# tides2_v40.net
KiCad netlist of a schematic drawn in EAGLE
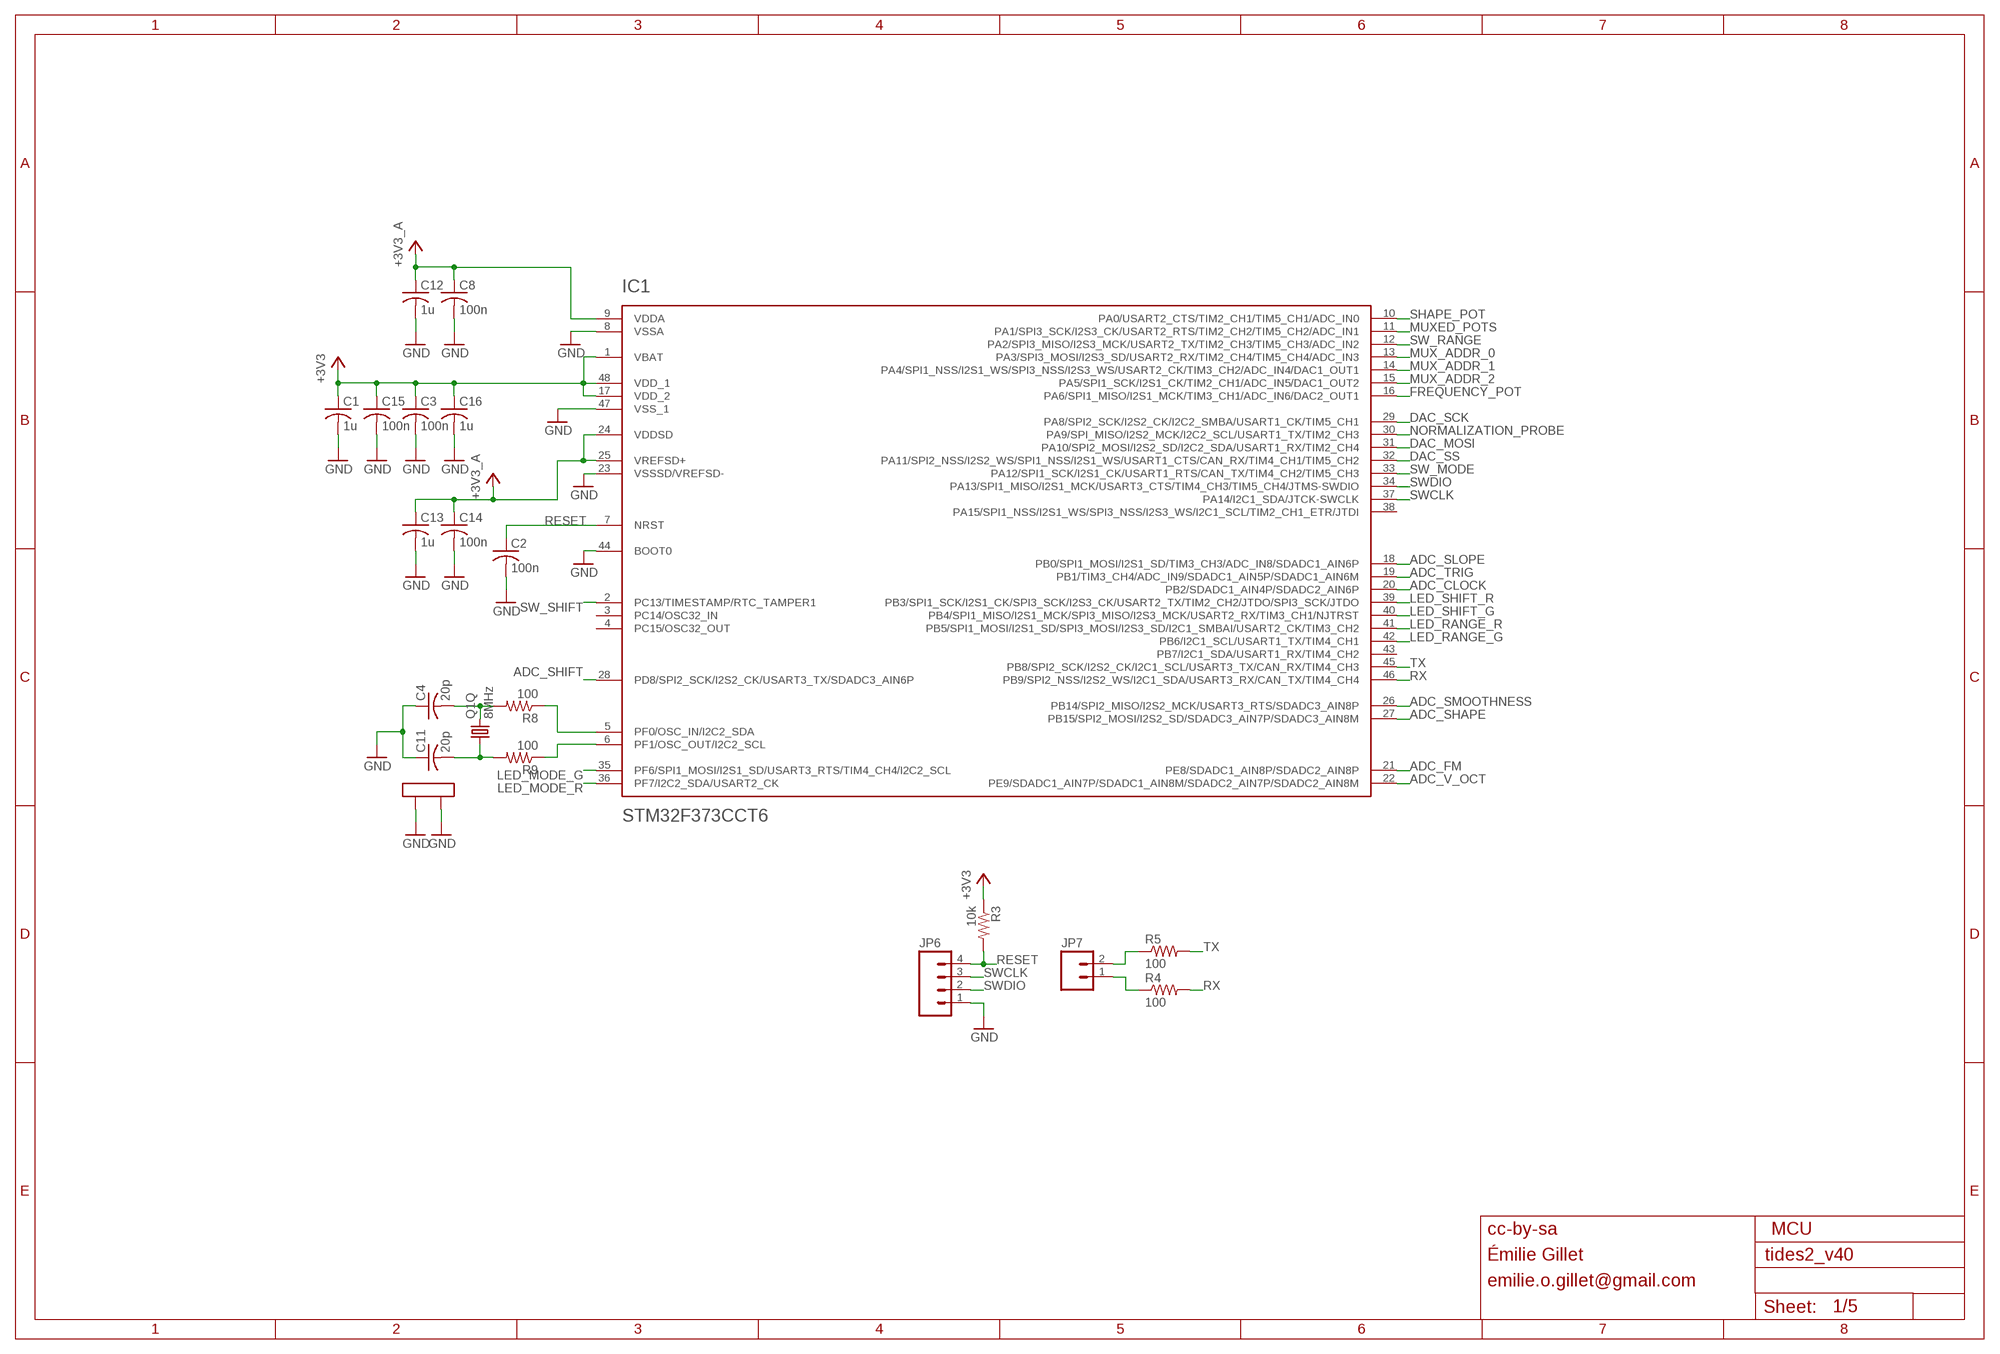
[diagram p0: schematic, sheet 1]
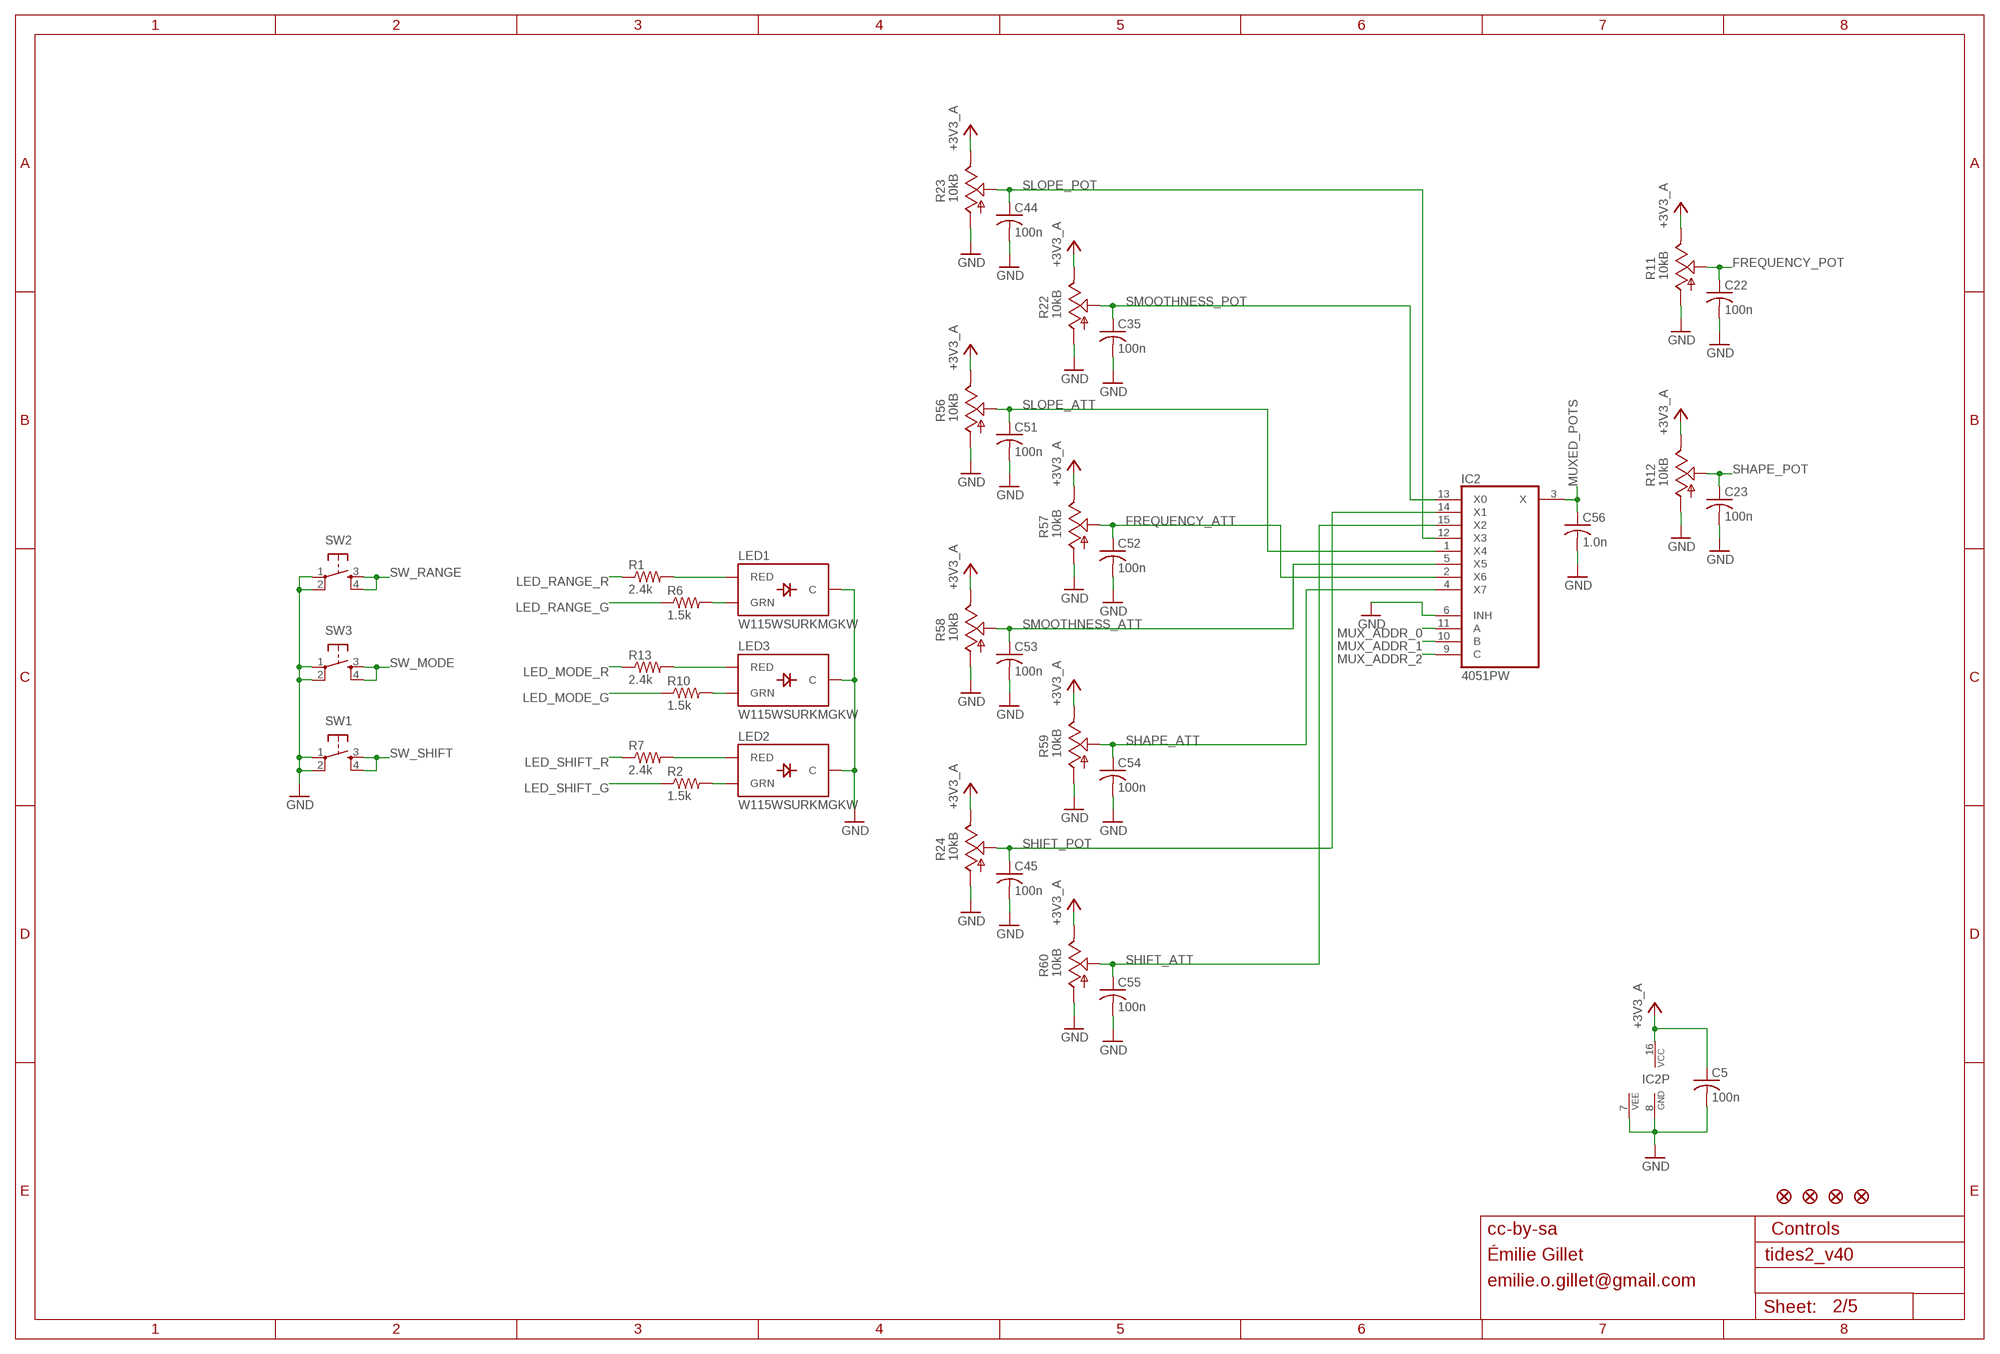
[diagram p1: schematic, sheet 2]
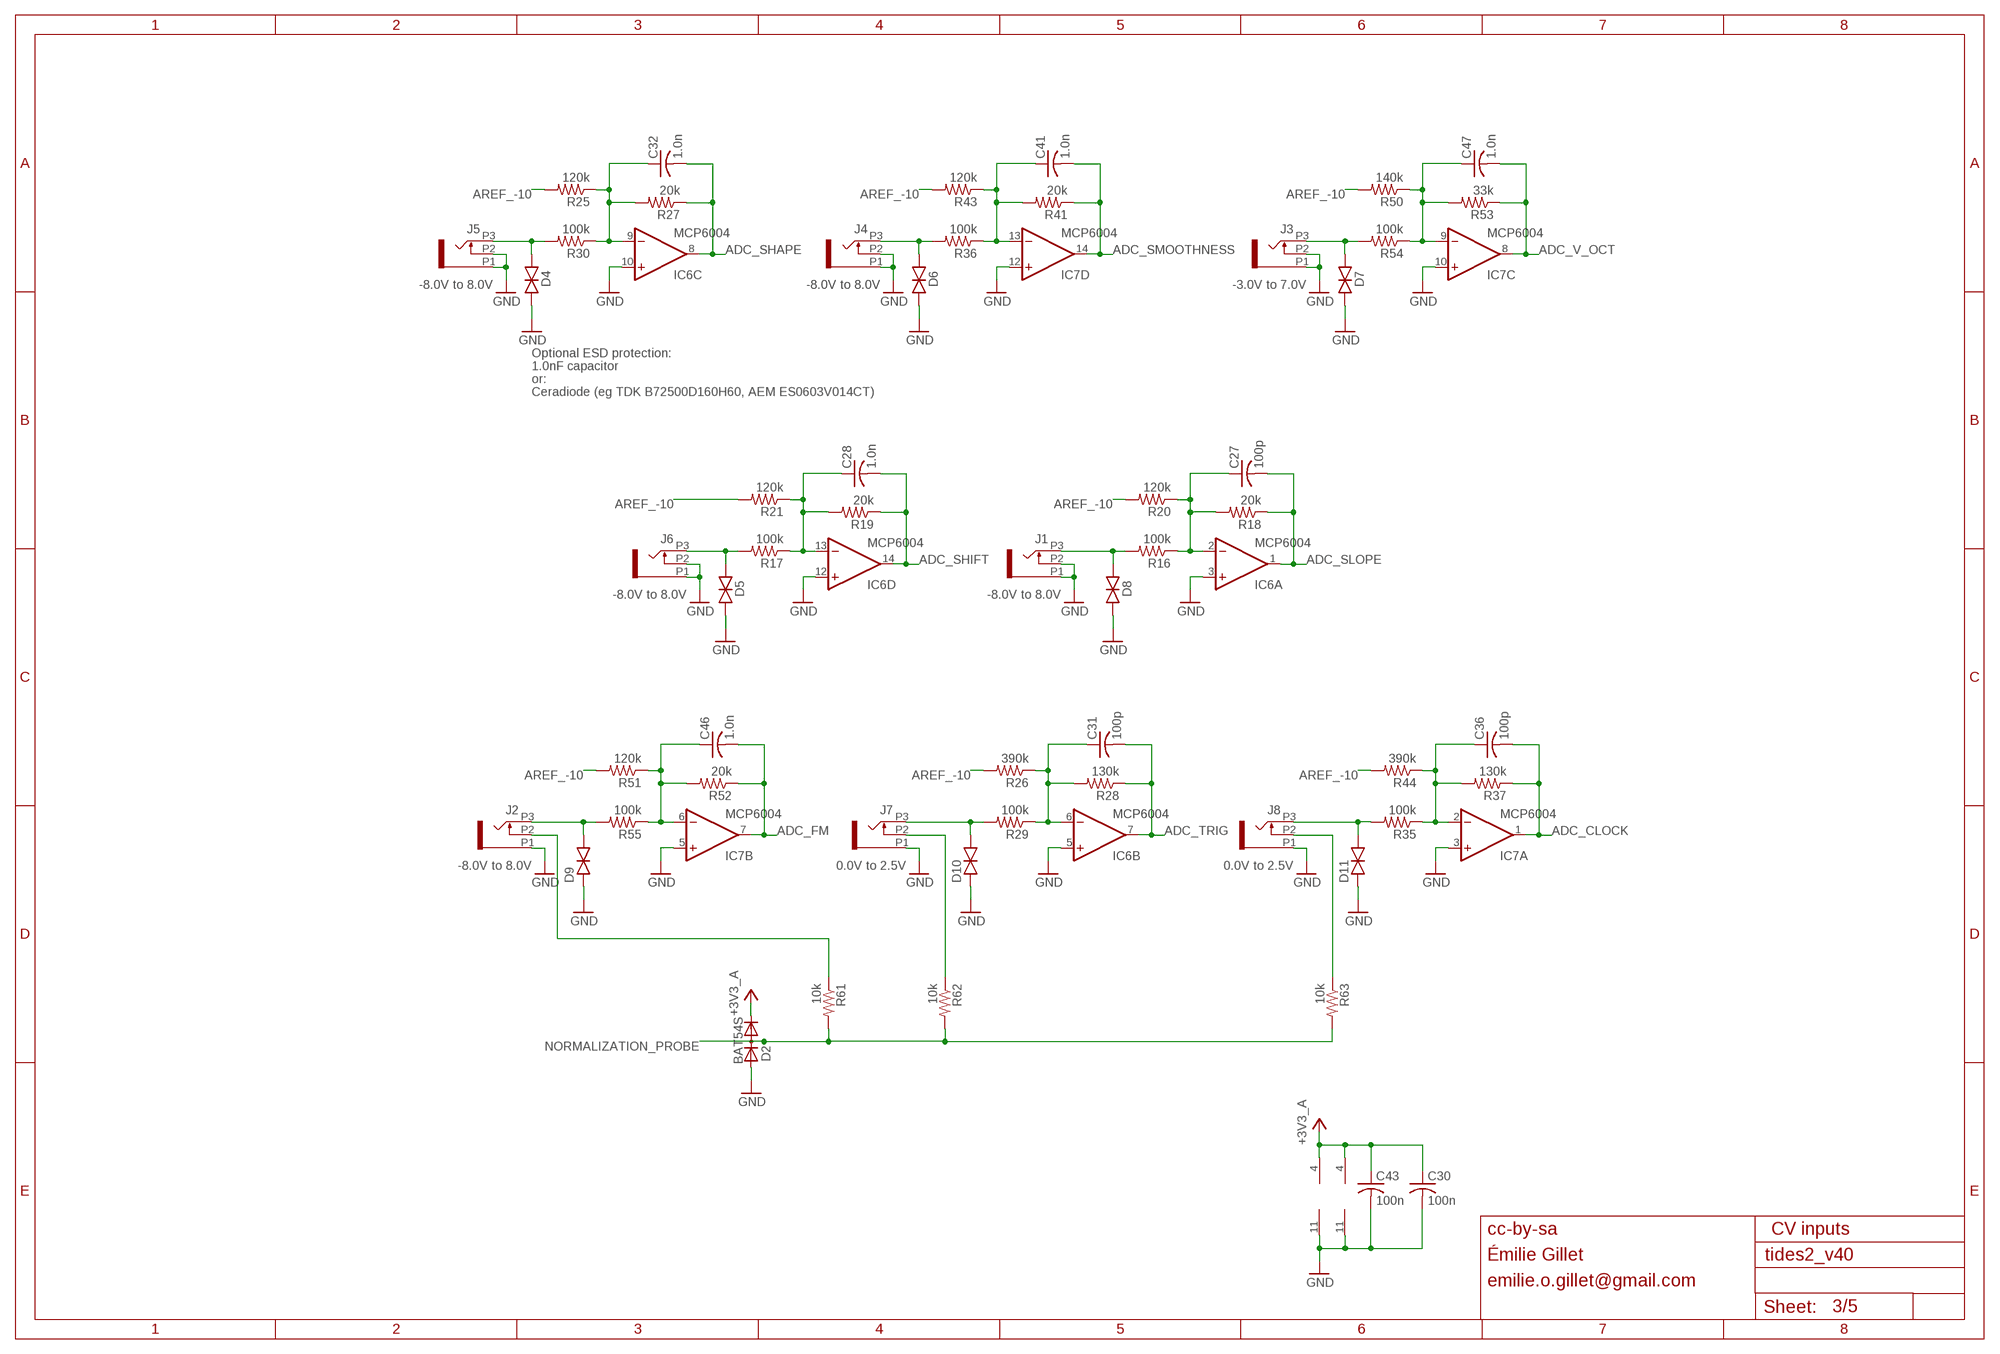
[diagram p2: schematic, sheet 3]
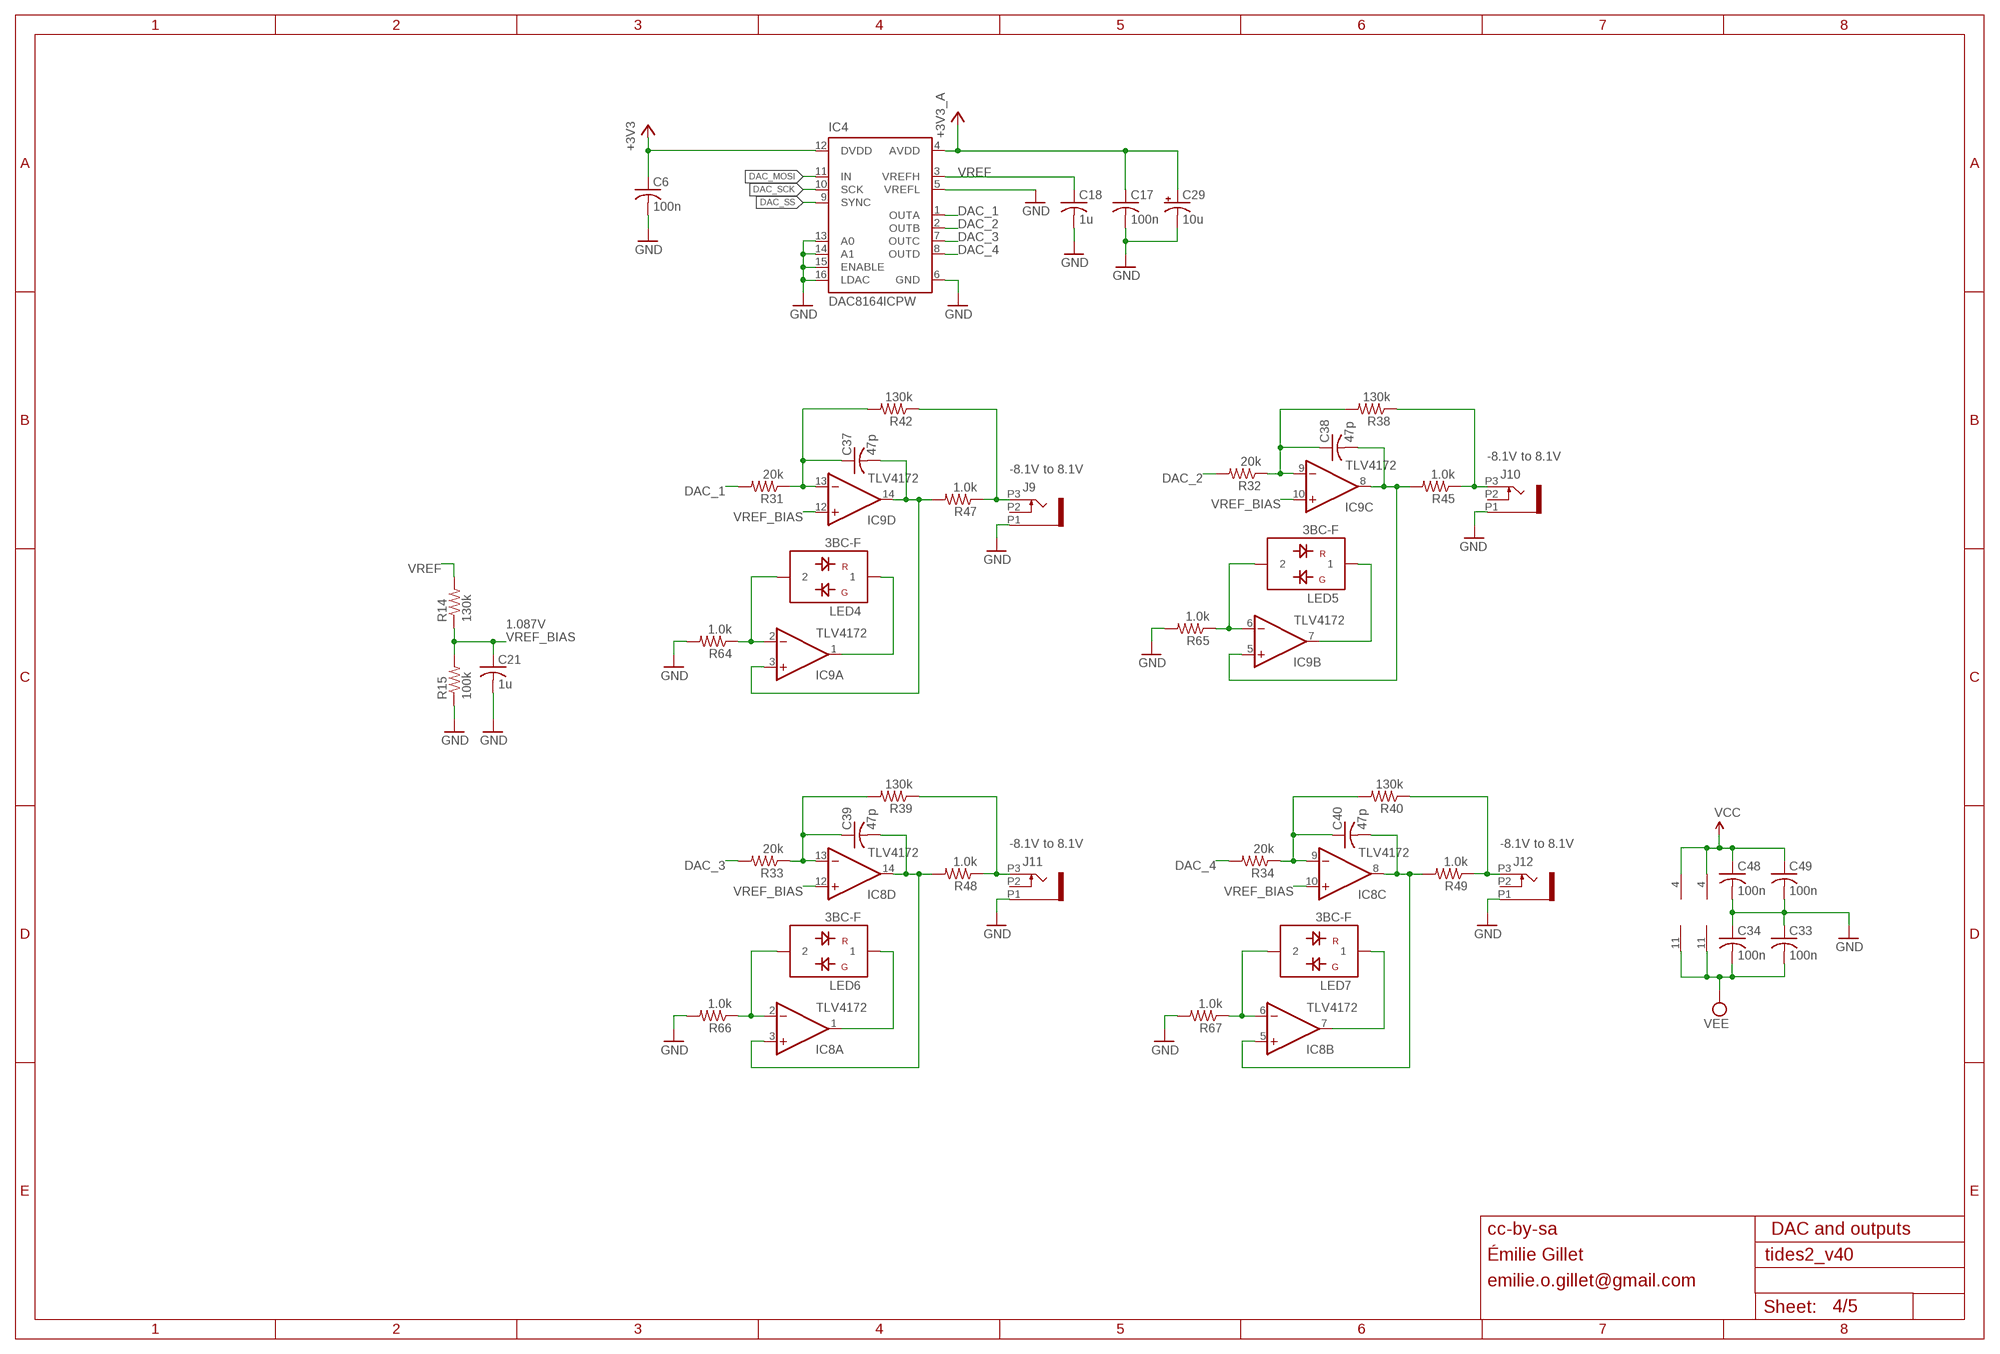
[diagram p3: schematic, sheet 4]
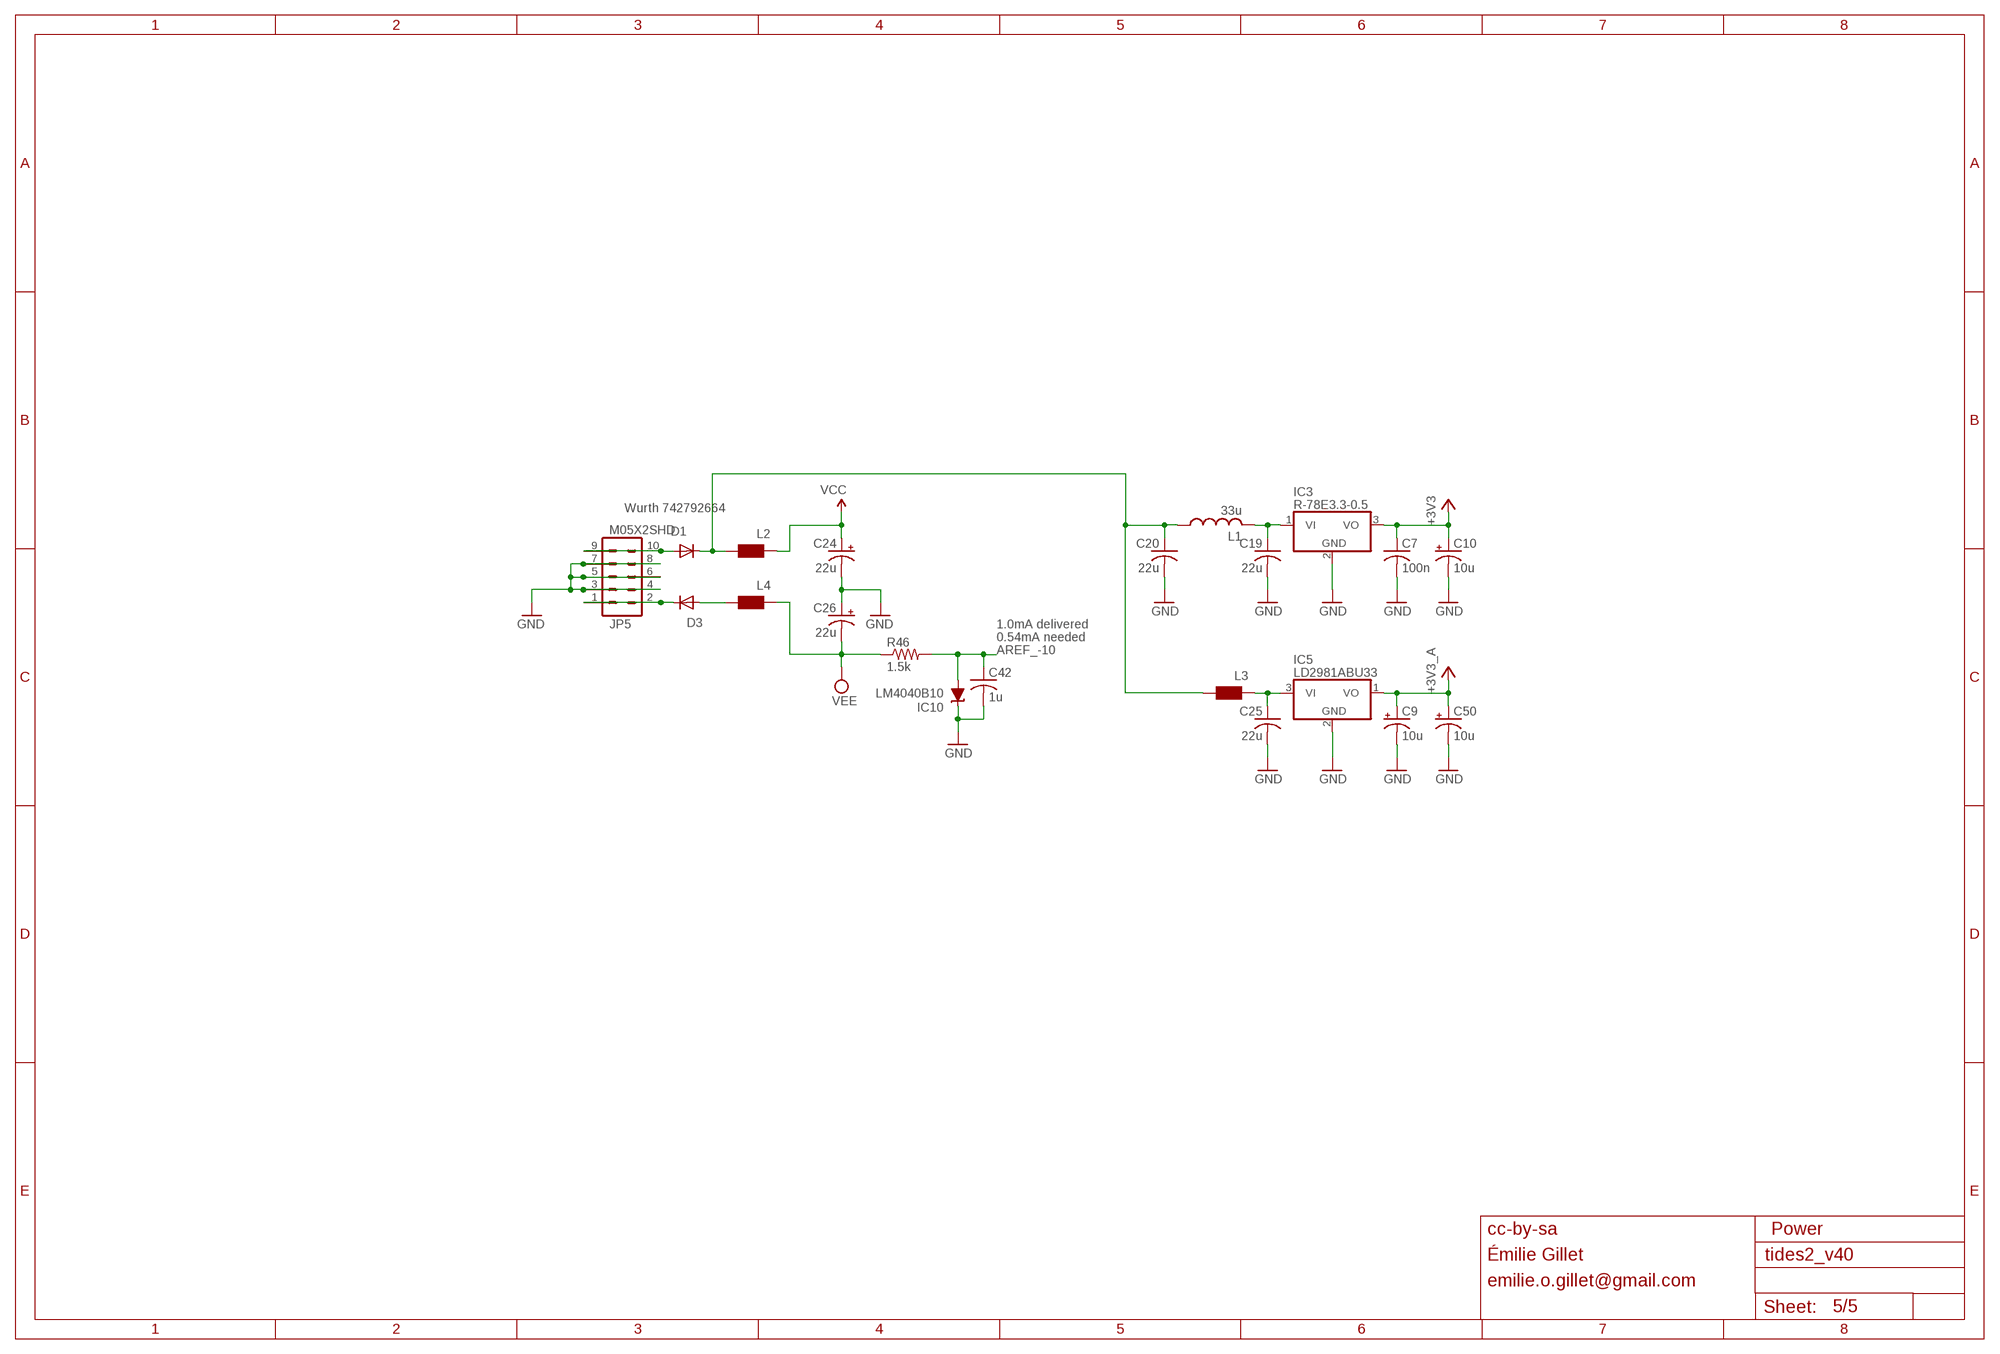
[diagram p4: schematic, sheet 5]

(export (version "E")
  (design (tool "Eeschema 10.0.6"))
  (components
    (comp (ref "C1")
      (value "1u")
      (footprint "eagle-import:C0402")
      (libsource (lib "eagle-import") (part "C-USC0402"))
    )
    (comp (ref "C2")
      (value "100n")
      (footprint "eagle-import:C0402")
      (libsource (lib "eagle-import") (part "C-USC0402"))
    )
    (comp (ref "C3")
      (value "100n")
      (footprint "eagle-import:C0402")
      (libsource (lib "eagle-import") (part "C-USC0402"))
    )
    (comp (ref "C4")
      (value "20p")
      (footprint "eagle-import:C0402")
      (libsource (lib "eagle-import") (part "C-USC0402"))
    )
    (comp (ref "C8")
      (value "100n")
      (footprint "eagle-import:C0402")
      (libsource (lib "eagle-import") (part "C-USC0402"))
    )
    (comp (ref "C11")
      (value "20p")
      (footprint "eagle-import:C0402")
      (libsource (lib "eagle-import") (part "C-USC0402"))
    )
    (comp (ref "C12")
      (value "1u")
      (footprint "eagle-import:C0402")
      (libsource (lib "eagle-import") (part "C-USC0402"))
    )
    (comp (ref "C13")
      (value "1u")
      (footprint "eagle-import:C0402")
      (libsource (lib "eagle-import") (part "C-USC0402"))
    )
    (comp (ref "C14")
      (value "100n")
      (footprint "eagle-import:C0402")
      (libsource (lib "eagle-import") (part "C-USC0402"))
    )
    (comp (ref "C15")
      (value "100n")
      (footprint "eagle-import:C0402")
      (libsource (lib "eagle-import") (part "C-USC0402"))
    )
    (comp (ref "C16")
      (value "1u")
      (footprint "eagle-import:C0402")
      (libsource (lib "eagle-import") (part "C-USC0402"))
    )
    (comp (ref "IC1")
      (value "STM32F373CCT6")
      (footprint "eagle-import:LQFP48")
      (libsource (lib "eagle-import") (part "STM32F373C"))
    )
    (comp (ref "JP6")
      (value "M04PTH")
      (footprint "eagle-import:1X04")
      (libsource (lib "eagle-import") (part "M04PTH"))
    )
    (comp (ref "JP7")
      (value "M02PTH")
      (footprint "eagle-import:1X02")
      (libsource (lib "eagle-import") (part "M02PTH"))
    )
    (comp (ref "Q1")
      (value "8MHz")
      (footprint "eagle-import:CTS406")
      (libsource (lib "eagle-import") (part "CRYSTAL"))
    )
    (comp (ref "R3")
      (value "10k")
      (footprint "eagle-import:R0402")
      (libsource (lib "eagle-import") (part "R-US_R0402"))
    )
    (comp (ref "R4")
      (value "100")
      (footprint "eagle-import:R0402")
      (libsource (lib "eagle-import") (part "R-US_R0402"))
    )
    (comp (ref "R5")
      (value "100")
      (footprint "eagle-import:R0402")
      (libsource (lib "eagle-import") (part "R-US_R0402"))
    )
    (comp (ref "R8")
      (value "100")
      (footprint "eagle-import:R0402")
      (libsource (lib "eagle-import") (part "R-US_R0402"))
    )
    (comp (ref "R9")
      (value "100")
      (footprint "eagle-import:R0402")
      (libsource (lib "eagle-import") (part "R-US_R0402"))
    )
    (comp (ref "C5")
      (value "100n")
      (footprint "eagle-import:C0402")
      (libsource (lib "eagle-import") (part "C-USC0402"))
    )
    (comp (ref "C22")
      (value "100n")
      (footprint "eagle-import:C0402")
      (libsource (lib "eagle-import") (part "C-USC0402"))
    )
    (comp (ref "C23")
      (value "100n")
      (footprint "eagle-import:C0402")
      (libsource (lib "eagle-import") (part "C-USC0402"))
    )
    (comp (ref "C35")
      (value "100n")
      (footprint "eagle-import:C0402")
      (libsource (lib "eagle-import") (part "C-USC0402"))
    )
    (comp (ref "C44")
      (value "100n")
      (footprint "eagle-import:C0402")
      (libsource (lib "eagle-import") (part "C-USC0402"))
    )
    (comp (ref "C45")
      (value "100n")
      (footprint "eagle-import:C0402")
      (libsource (lib "eagle-import") (part "C-USC0402"))
    )
    (comp (ref "C51")
      (value "100n")
      (footprint "eagle-import:C0402")
      (libsource (lib "eagle-import") (part "C-USC0402"))
    )
    (comp (ref "C52")
      (value "100n")
      (footprint "eagle-import:C0402")
      (libsource (lib "eagle-import") (part "C-USC0402"))
    )
    (comp (ref "C53")
      (value "100n")
      (footprint "eagle-import:C0402")
      (libsource (lib "eagle-import") (part "C-USC0402"))
    )
    (comp (ref "C54")
      (value "100n")
      (footprint "eagle-import:C0402")
      (libsource (lib "eagle-import") (part "C-USC0402"))
    )
    (comp (ref "C55")
      (value "100n")
      (footprint "eagle-import:C0402")
      (libsource (lib "eagle-import") (part "C-USC0402"))
    )
    (comp (ref "C56")
      (value "1.0n")
      (footprint "eagle-import:C0402")
      (libsource (lib "eagle-import") (part "C-USC0402"))
    )
    (comp (ref "IC2")
      (value "4051PW")
      (footprint "eagle-import:TSSOP16_065")
      (libsource (lib "eagle-import") (part "4051PW"))
    )
    (comp (ref "JP1")
      (value "FIDUCIAL1X2")
      (footprint "eagle-import:FIDUCIAL-1X2")
      (libsource (lib "eagle-import") (part "FIDUCIAL1X2"))
    )
    (comp (ref "JP2")
      (value "FIDUCIAL1X2")
      (footprint "eagle-import:FIDUCIAL-1X2")
      (libsource (lib "eagle-import") (part "FIDUCIAL1X2"))
    )
    (comp (ref "JP3")
      (value "FIDUCIAL1X2")
      (footprint "eagle-import:FIDUCIAL-1X2")
      (libsource (lib "eagle-import") (part "FIDUCIAL1X2"))
    )
    (comp (ref "JP4")
      (value "FIDUCIAL1X2")
      (footprint "eagle-import:FIDUCIAL-1X2")
      (libsource (lib "eagle-import") (part "FIDUCIAL1X2"))
    )
    (comp (ref "LED1")
      (value "W115WSURKMGKW")
      (footprint "eagle-import:LED-BICOLOR-THROUGHHOLE-2.54")
      (libsource (lib "eagle-import") (part "LED-BICOLOR-THROUGHHOLE2.54"))
    )
    (comp (ref "LED2")
      (value "W115WSURKMGKW")
      (footprint "eagle-import:LED-BICOLOR-THROUGHHOLE-2.54")
      (libsource (lib "eagle-import") (part "LED-BICOLOR-THROUGHHOLE2.54"))
    )
    (comp (ref "LED3")
      (value "W115WSURKMGKW")
      (footprint "eagle-import:LED-BICOLOR-THROUGHHOLE-2.54")
      (libsource (lib "eagle-import") (part "LED-BICOLOR-THROUGHHOLE2.54"))
    )
    (comp (ref "R1")
      (value "2.4k")
      (footprint "eagle-import:R0402")
      (libsource (lib "eagle-import") (part "R-US_R0402"))
    )
    (comp (ref "R2")
      (value "1.5k")
      (footprint "eagle-import:R0402")
      (libsource (lib "eagle-import") (part "R-US_R0402"))
    )
    (comp (ref "R6")
      (value "1.5k")
      (footprint "eagle-import:R0402")
      (libsource (lib "eagle-import") (part "R-US_R0402"))
    )
    (comp (ref "R7")
      (value "2.4k")
      (footprint "eagle-import:R0402")
      (libsource (lib "eagle-import") (part "R-US_R0402"))
    )
    (comp (ref "R10")
      (value "1.5k")
      (footprint "eagle-import:R0402")
      (libsource (lib "eagle-import") (part "R-US_R0402"))
    )
    (comp (ref "R11")
      (value "10kB")
      (footprint "eagle-import:ALPS_POT_VERTICAL_PS")
      (libsource (lib "eagle-import") (part "POT_USVERTICAL_PS"))
    )
    (comp (ref "R12")
      (value "10kB")
      (footprint "eagle-import:ALPS_POT_VERTICAL_PS")
      (libsource (lib "eagle-import") (part "POT_USVERTICAL_PS"))
    )
    (comp (ref "R13")
      (value "2.4k")
      (footprint "eagle-import:R0402")
      (libsource (lib "eagle-import") (part "R-US_R0402"))
    )
    (comp (ref "R22")
      (value "10kB")
      (footprint "eagle-import:ALPS_POT_VERTICAL_PS")
      (libsource (lib "eagle-import") (part "POT_USVERTICAL_PS"))
    )
    (comp (ref "R23")
      (value "10kB")
      (footprint "eagle-import:ALPS_POT_VERTICAL_PS")
      (libsource (lib "eagle-import") (part "POT_USVERTICAL_PS"))
    )
    (comp (ref "R24")
      (value "10kB")
      (footprint "eagle-import:ALPS_POT_VERTICAL_PS")
      (libsource (lib "eagle-import") (part "POT_USVERTICAL_PS"))
    )
    (comp (ref "R56")
      (value "10kB")
      (footprint "eagle-import:ALPS_POT_VERTICAL")
      (libsource (lib "eagle-import") (part "POT_USVERTICAL"))
    )
    (comp (ref "R57")
      (value "10kB")
      (footprint "eagle-import:ALPS_POT_VERTICAL")
      (libsource (lib "eagle-import") (part "POT_USVERTICAL"))
    )
    (comp (ref "R58")
      (value "10kB")
      (footprint "eagle-import:ALPS_POT_VERTICAL")
      (libsource (lib "eagle-import") (part "POT_USVERTICAL"))
    )
    (comp (ref "R59")
      (value "10kB")
      (footprint "eagle-import:ALPS_POT_VERTICAL")
      (libsource (lib "eagle-import") (part "POT_USVERTICAL"))
    )
    (comp (ref "R60")
      (value "10kB")
      (footprint "eagle-import:ALPS_POT_VERTICAL")
      (libsource (lib "eagle-import") (part "POT_USVERTICAL"))
    )
    (comp (ref "SW1")
      (value "TAC_SWITCHPTH")
      (footprint "eagle-import:TACTILE-PTH")
      (libsource (lib "eagle-import") (part "TAC_SWITCHPTH"))
    )
    (comp (ref "SW2")
      (value "TAC_SWITCHPTH")
      (footprint "eagle-import:TACTILE-PTH")
      (libsource (lib "eagle-import") (part "TAC_SWITCHPTH"))
    )
    (comp (ref "SW3")
      (value "TAC_SWITCHPTH")
      (footprint "eagle-import:TACTILE-PTH")
      (libsource (lib "eagle-import") (part "TAC_SWITCHPTH"))
    )
    (comp (ref "C7")
      (value "100n")
      (footprint "eagle-import:C0402")
      (libsource (lib "eagle-import") (part "C-USC0402"))
    )
    (comp (ref "C9")
      (value "10u")
      (footprint "eagle-import:PANASONIC_A")
      (libsource (lib "eagle-import") (part "CPOL-USA"))
    )
    (comp (ref "C10")
      (value "10u")
      (footprint "eagle-import:PANASONIC_A")
      (libsource (lib "eagle-import") (part "CPOL-USA"))
    )
    (comp (ref "C19")
      (value "22u")
      (footprint "eagle-import:C1206")
      (libsource (lib "eagle-import") (part "C-USC1206"))
    )
    (comp (ref "C20")
      (value "22u")
      (footprint "eagle-import:C1206")
      (libsource (lib "eagle-import") (part "C-USC1206"))
    )
    (comp (ref "C24")
      (value "22u")
      (footprint "eagle-import:PANASONIC_B")
      (libsource (lib "eagle-import") (part "CPOL-USB"))
    )
    (comp (ref "C25")
      (value "22u")
      (footprint "eagle-import:C1206")
      (libsource (lib "eagle-import") (part "C-USC1206"))
    )
    (comp (ref "C26")
      (value "22u")
      (footprint "eagle-import:PANASONIC_B")
      (libsource (lib "eagle-import") (part "CPOL-USB"))
    )
    (comp (ref "C42")
      (value "1u")
      (footprint "eagle-import:C0402")
      (libsource (lib "eagle-import") (part "C-USC0402"))
    )
    (comp (ref "C50")
      (value "10u")
      (footprint "eagle-import:PANASONIC_A")
      (libsource (lib "eagle-import") (part "CPOL-USA"))
    )
    (comp (ref "D1")
      (value "1N5819HW")
      (footprint "eagle-import:SOD123")
      (libsource (lib "eagle-import") (part "DIODE-SOD123"))
    )
    (comp (ref "D3")
      (value "1N5819HW")
      (footprint "eagle-import:SOD123")
      (libsource (lib "eagle-import") (part "DIODE-SOD123"))
    )
    (comp (ref "IC3")
      (value "R-78E3.3-0.5")
      (footprint "eagle-import:WE78")
      (libsource (lib "eagle-import") (part "WE173950378"))
    )
    (comp (ref "IC5")
      (value "LD2981ABU33")
      (footprint "eagle-import:SOT89")
      (libsource (lib "eagle-import") (part "LD2981ABU"))
    )
    (comp (ref "IC10")
      (value "LM4040B10")
      (footprint "eagle-import:DBZ_R-PDSO-G3")
      (libsource (lib "eagle-import") (part "LM4041DBZB12"))
    )
    (comp (ref "JP5")
      (value "M05X2SHD")
      (footprint "eagle-import:2X5-SHROUDED")
      (libsource (lib "eagle-import") (part "M05X2SHD"))
    )
    (comp (ref "L1")
      (value "33u")
      (footprint "eagle-import:L2012C")
      (libsource (lib "eagle-import") (part "L-USL2012C"))
    )
    (comp (ref "L2")
      (value "WE-CBF_0603")
      (footprint "eagle-import:0603")
      (libsource (lib "eagle-import") (part "WE-CBF_0603"))
    )
    (comp (ref "L3")
      (value "WE-CBF_0603")
      (footprint "eagle-import:0603")
      (libsource (lib "eagle-import") (part "WE-CBF_0603"))
    )
    (comp (ref "L4")
      (value "WE-CBF_0603")
      (footprint "eagle-import:0603")
      (libsource (lib "eagle-import") (part "WE-CBF_0603"))
    )
    (comp (ref "R46")
      (value "1.5k")
      (footprint "eagle-import:R0402")
      (libsource (lib "eagle-import") (part "R-US_R0402"))
    )
    (comp (ref "C27")
      (value "100p")
      (footprint "eagle-import:C0402")
      (libsource (lib "eagle-import") (part "C-USC0402"))
    )
    (comp (ref "C28")
      (value "1.0n")
      (footprint "eagle-import:C0402")
      (libsource (lib "eagle-import") (part "C-USC0402"))
    )
    (comp (ref "C30")
      (value "100n")
      (footprint "eagle-import:C0402")
      (libsource (lib "eagle-import") (part "C-USC0402"))
    )
    (comp (ref "C31")
      (value "100p")
      (footprint "eagle-import:C0402")
      (libsource (lib "eagle-import") (part "C-USC0402"))
    )
    (comp (ref "C32")
      (value "1.0n")
      (footprint "eagle-import:C0402")
      (libsource (lib "eagle-import") (part "C-USC0402"))
    )
    (comp (ref "C36")
      (value "100p")
      (footprint "eagle-import:C0402")
      (libsource (lib "eagle-import") (part "C-USC0402"))
    )
    (comp (ref "C41")
      (value "1.0n")
      (footprint "eagle-import:C0402")
      (libsource (lib "eagle-import") (part "C-USC0402"))
    )
    (comp (ref "C43")
      (value "100n")
      (footprint "eagle-import:C0402")
      (libsource (lib "eagle-import") (part "C-USC0402"))
    )
    (comp (ref "C46")
      (value "1.0n")
      (footprint "eagle-import:C0402")
      (libsource (lib "eagle-import") (part "C-USC0402"))
    )
    (comp (ref "C47")
      (value "1.0n")
      (footprint "eagle-import:C0402")
      (libsource (lib "eagle-import") (part "C-USC0402"))
    )
    (comp (ref "D2")
      (value "BAT54S")
      (footprint "eagle-import:SOT23")
      (libsource (lib "eagle-import") (part "DIODE_2CACA-SOT23"))
    )
    (comp (ref "D4")
      (value "TVS")
      (footprint "eagle-import:0603")
      (libsource (lib "eagle-import") (part "TVS"))
    )
    (comp (ref "D5")
      (value "TVS")
      (footprint "eagle-import:0603")
      (libsource (lib "eagle-import") (part "TVS"))
    )
    (comp (ref "D6")
      (value "TVS")
      (footprint "eagle-import:0603")
      (libsource (lib "eagle-import") (part "TVS"))
    )
    (comp (ref "D7")
      (value "TVS")
      (footprint "eagle-import:0603")
      (libsource (lib "eagle-import") (part "TVS"))
    )
    (comp (ref "D8")
      (value "TVS")
      (footprint "eagle-import:0603")
      (libsource (lib "eagle-import") (part "TVS"))
    )
    (comp (ref "D9")
      (value "TVS")
      (footprint "eagle-import:0603")
      (libsource (lib "eagle-import") (part "TVS"))
    )
    (comp (ref "D10")
      (value "TVS")
      (footprint "eagle-import:0603")
      (libsource (lib "eagle-import") (part "TVS"))
    )
    (comp (ref "D11")
      (value "TVS")
      (footprint "eagle-import:0603")
      (libsource (lib "eagle-import") (part "TVS"))
    )
    (comp (ref "IC6")
      (value "MCP6004")
      (footprint "eagle-import:TSSOP14_065")
      (libsource (lib "eagle-import") (part "TL074PW"))
    )
    (comp (ref "IC7")
      (value "MCP6004")
      (footprint "eagle-import:TSSOP14_065")
      (libsource (lib "eagle-import") (part "TL074PW"))
    )
    (comp (ref "J1")
      (value "PJ301_THONKICONN6")
      (footprint "eagle-import:WQP_PJ_301M6")
      (libsource (lib "eagle-import") (part "og-pj301_variations_PJ301_THONKICONN6"))
    )
    (comp (ref "J2")
      (value "PJ301_THONKICONN6")
      (footprint "eagle-import:WQP_PJ_301M6")
      (libsource (lib "eagle-import") (part "og-pj301_variations_PJ301_THONKICONN6"))
    )
    (comp (ref "J3")
      (value "PJ301_THONKICONN6")
      (footprint "eagle-import:WQP_PJ_301M6")
      (libsource (lib "eagle-import") (part "og-pj301_variations_PJ301_THONKICONN6"))
    )
    (comp (ref "J4")
      (value "PJ301_THONKICONN6")
      (footprint "eagle-import:WQP_PJ_301M6")
      (libsource (lib "eagle-import") (part "og-pj301_variations_PJ301_THONKICONN6"))
    )
    (comp (ref "J5")
      (value "PJ301_THONKICONN6")
      (footprint "eagle-import:WQP_PJ_301M6")
      (libsource (lib "eagle-import") (part "og-pj301_variations_PJ301_THONKICONN6"))
    )
    (comp (ref "J6")
      (value "PJ301_THONKICONN6")
      (footprint "eagle-import:WQP_PJ_301M6")
      (libsource (lib "eagle-import") (part "og-pj301_variations_PJ301_THONKICONN6"))
    )
    (comp (ref "J7")
      (value "PJ301_THONKICONN6")
      (footprint "eagle-import:WQP_PJ_301M6")
      (libsource (lib "eagle-import") (part "og-pj301_variations_PJ301_THONKICONN6"))
    )
    (comp (ref "J8")
      (value "PJ301_THONKICONN6")
      (footprint "eagle-import:WQP_PJ_301M6")
      (libsource (lib "eagle-import") (part "og-pj301_variations_PJ301_THONKICONN6"))
    )
    (comp (ref "R16")
      (value "100k")
      (footprint "eagle-import:R0402")
      (libsource (lib "eagle-import") (part "R-US_R0402"))
    )
    (comp (ref "R17")
      (value "100k")
      (footprint "eagle-import:R0402")
      (libsource (lib "eagle-import") (part "R-US_R0402"))
    )
    (comp (ref "R18")
      (value "20k")
      (footprint "eagle-import:R0402")
      (libsource (lib "eagle-import") (part "R-US_R0402"))
    )
    (comp (ref "R19")
      (value "20k")
      (footprint "eagle-import:R0402")
      (libsource (lib "eagle-import") (part "R-US_R0402"))
    )
    (comp (ref "R20")
      (value "120k")
      (footprint "eagle-import:R0402")
      (libsource (lib "eagle-import") (part "R-US_R0402"))
    )
    (comp (ref "R21")
      (value "120k")
      (footprint "eagle-import:R0402")
      (libsource (lib "eagle-import") (part "R-US_R0402"))
    )
    (comp (ref "R25")
      (value "120k")
      (footprint "eagle-import:R0402")
      (libsource (lib "eagle-import") (part "R-US_R0402"))
    )
    (comp (ref "R26")
      (value "390k")
      (footprint "eagle-import:R0402")
      (libsource (lib "eagle-import") (part "R-US_R0402"))
    )
    (comp (ref "R27")
      (value "20k")
      (footprint "eagle-import:R0402")
      (libsource (lib "eagle-import") (part "R-US_R0402"))
    )
    (comp (ref "R28")
      (value "130k")
      (footprint "eagle-import:R0402")
      (libsource (lib "eagle-import") (part "R-US_R0402"))
    )
    (comp (ref "R29")
      (value "100k")
      (footprint "eagle-import:R0402")
      (libsource (lib "eagle-import") (part "R-US_R0402"))
    )
    (comp (ref "R30")
      (value "100k")
      (footprint "eagle-import:R0402")
      (libsource (lib "eagle-import") (part "R-US_R0402"))
    )
    (comp (ref "R35")
      (value "100k")
      (footprint "eagle-import:R0402")
      (libsource (lib "eagle-import") (part "R-US_R0402"))
    )
    (comp (ref "R36")
      (value "100k")
      (footprint "eagle-import:R0402")
      (libsource (lib "eagle-import") (part "R-US_R0402"))
    )
    (comp (ref "R37")
      (value "130k")
      (footprint "eagle-import:R0402")
      (libsource (lib "eagle-import") (part "R-US_R0402"))
    )
    (comp (ref "R41")
      (value "20k")
      (footprint "eagle-import:R0402")
      (libsource (lib "eagle-import") (part "R-US_R0402"))
    )
    (comp (ref "R43")
      (value "120k")
      (footprint "eagle-import:R0402")
      (libsource (lib "eagle-import") (part "R-US_R0402"))
    )
    (comp (ref "R44")
      (value "390k")
      (footprint "eagle-import:R0402")
      (libsource (lib "eagle-import") (part "R-US_R0402"))
    )
    (comp (ref "R50")
      (value "140k")
      (footprint "eagle-import:R0402")
      (libsource (lib "eagle-import") (part "R-US_R0402"))
    )
    (comp (ref "R51")
      (value "120k")
      (footprint "eagle-import:R0402")
      (libsource (lib "eagle-import") (part "R-US_R0402"))
    )
    (comp (ref "R52")
      (value "20k")
      (footprint "eagle-import:R0402")
      (libsource (lib "eagle-import") (part "R-US_R0402"))
    )
    (comp (ref "R53")
      (value "33k")
      (footprint "eagle-import:R0402")
      (libsource (lib "eagle-import") (part "R-US_R0402"))
    )
    (comp (ref "R54")
      (value "100k")
      (footprint "eagle-import:R0402")
      (libsource (lib "eagle-import") (part "R-US_R0402"))
    )
    (comp (ref "R55")
      (value "100k")
      (footprint "eagle-import:R0402")
      (libsource (lib "eagle-import") (part "R-US_R0402"))
    )
    (comp (ref "R61")
      (value "10k")
      (footprint "eagle-import:R0402")
      (libsource (lib "eagle-import") (part "R-US_R0402"))
    )
    (comp (ref "R62")
      (value "10k")
      (footprint "eagle-import:R0402")
      (libsource (lib "eagle-import") (part "R-US_R0402"))
    )
    (comp (ref "R63")
      (value "10k")
      (footprint "eagle-import:R0402")
      (libsource (lib "eagle-import") (part "R-US_R0402"))
    )
    (comp (ref "C6")
      (value "100n")
      (footprint "eagle-import:C0402")
      (libsource (lib "eagle-import") (part "C-USC0402"))
    )
    (comp (ref "C17")
      (value "100n")
      (footprint "eagle-import:C0402")
      (libsource (lib "eagle-import") (part "C-USC0402"))
    )
    (comp (ref "C18")
      (value "1u")
      (footprint "eagle-import:C0402")
      (libsource (lib "eagle-import") (part "C-USC0402"))
    )
    (comp (ref "C21")
      (value "1u")
      (footprint "eagle-import:C0402")
      (libsource (lib "eagle-import") (part "C-USC0402"))
    )
    (comp (ref "C29")
      (value "10u")
      (footprint "eagle-import:PANASONIC_A")
      (libsource (lib "eagle-import") (part "CPOL-USA"))
    )
    (comp (ref "C33")
      (value "100n")
      (footprint "eagle-import:C0402")
      (libsource (lib "eagle-import") (part "C-USC0402"))
    )
    (comp (ref "C34")
      (value "100n")
      (footprint "eagle-import:C0402")
      (libsource (lib "eagle-import") (part "C-USC0402"))
    )
    (comp (ref "C37")
      (value "47p")
      (footprint "eagle-import:C0402")
      (libsource (lib "eagle-import") (part "C-USC0402"))
    )
    (comp (ref "C38")
      (value "47p")
      (footprint "eagle-import:C0402")
      (libsource (lib "eagle-import") (part "C-USC0402"))
    )
    (comp (ref "C39")
      (value "47p")
      (footprint "eagle-import:C0402")
      (libsource (lib "eagle-import") (part "C-USC0402"))
    )
    (comp (ref "C40")
      (value "47p")
      (footprint "eagle-import:C0402")
      (libsource (lib "eagle-import") (part "C-USC0402"))
    )
    (comp (ref "C48")
      (value "100n")
      (footprint "eagle-import:C0402")
      (libsource (lib "eagle-import") (part "C-USC0402"))
    )
    (comp (ref "C49")
      (value "100n")
      (footprint "eagle-import:C0402")
      (libsource (lib "eagle-import") (part "C-USC0402"))
    )
    (comp (ref "IC4")
      (value "DAC8164ICPW")
      (footprint "eagle-import:SOP65P640X110-16N")
      (libsource (lib "eagle-import") (part "DAC8564"))
    )
    (comp (ref "IC8")
      (value "TLV4172")
      (footprint "eagle-import:TSSOP14_065")
      (libsource (lib "eagle-import") (part "TL074PW"))
    )
    (comp (ref "IC9")
      (value "TLV4172")
      (footprint "eagle-import:TSSOP14_065")
      (libsource (lib "eagle-import") (part "TL074PW"))
    )
    (comp (ref "J9")
      (value "PJ301_THONKICONN6")
      (footprint "eagle-import:WQP_PJ_301M6")
      (libsource (lib "eagle-import") (part "PJ301_THONKICONN6"))
    )
    (comp (ref "J10")
      (value "PJ301_THONKICONN6")
      (footprint "eagle-import:WQP_PJ_301M6")
      (libsource (lib "eagle-import") (part "PJ301_THONKICONN6"))
    )
    (comp (ref "J11")
      (value "PJ301_THONKICONN6")
      (footprint "eagle-import:WQP_PJ_301M6")
      (libsource (lib "eagle-import") (part "PJ301_THONKICONN6"))
    )
    (comp (ref "J12")
      (value "PJ301_THONKICONN6")
      (footprint "eagle-import:WQP_PJ_301M6")
      (libsource (lib "eagle-import") (part "PJ301_THONKICONN6"))
    )
    (comp (ref "LED4")
      (value "3BC-F")
      (footprint "eagle-import:LED3MM")
      (libsource (lib "eagle-import") (part "LED-BICOLOR-SHARED-THROUGHHOLE"))
    )
    (comp (ref "LED5")
      (value "3BC-F")
      (footprint "eagle-import:LED3MM")
      (libsource (lib "eagle-import") (part "LED-BICOLOR-SHARED-THROUGHHOLE"))
    )
    (comp (ref "LED6")
      (value "3BC-F")
      (footprint "eagle-import:LED3MM")
      (libsource (lib "eagle-import") (part "LED-BICOLOR-SHARED-THROUGHHOLE"))
    )
    (comp (ref "LED7")
      (value "3BC-F")
      (footprint "eagle-import:LED3MM")
      (libsource (lib "eagle-import") (part "LED-BICOLOR-SHARED-THROUGHHOLE"))
    )
    (comp (ref "R14")
      (value "130k")
      (footprint "eagle-import:R0402")
      (libsource (lib "eagle-import") (part "R-US_R0402"))
    )
    (comp (ref "R15")
      (value "100k")
      (footprint "eagle-import:R0402")
      (libsource (lib "eagle-import") (part "R-US_R0402"))
    )
    (comp (ref "R31")
      (value "20k")
      (footprint "eagle-import:R0402")
      (libsource (lib "eagle-import") (part "R-US_R0402"))
    )
    (comp (ref "R32")
      (value "20k")
      (footprint "eagle-import:R0402")
      (libsource (lib "eagle-import") (part "R-US_R0402"))
    )
    (comp (ref "R33")
      (value "20k")
      (footprint "eagle-import:R0402")
      (libsource (lib "eagle-import") (part "R-US_R0402"))
    )
    (comp (ref "R34")
      (value "20k")
      (footprint "eagle-import:R0402")
      (libsource (lib "eagle-import") (part "R-US_R0402"))
    )
    (comp (ref "R38")
      (value "130k")
      (footprint "eagle-import:R0402")
      (libsource (lib "eagle-import") (part "R-US_R0402"))
    )
    (comp (ref "R39")
      (value "130k")
      (footprint "eagle-import:R0402")
      (libsource (lib "eagle-import") (part "R-US_R0402"))
    )
    (comp (ref "R40")
      (value "130k")
      (footprint "eagle-import:R0402")
      (libsource (lib "eagle-import") (part "R-US_R0402"))
    )
    (comp (ref "R42")
      (value "130k")
      (footprint "eagle-import:R0402")
      (libsource (lib "eagle-import") (part "R-US_R0402"))
    )
    (comp (ref "R45")
      (value "1.0k")
      (footprint "eagle-import:R0603")
      (libsource (lib "eagle-import") (part "R-US_R0603"))
    )
    (comp (ref "R47")
      (value "1.0k")
      (footprint "eagle-import:R0603")
      (libsource (lib "eagle-import") (part "R-US_R0603"))
    )
    (comp (ref "R48")
      (value "1.0k")
      (footprint "eagle-import:R0603")
      (libsource (lib "eagle-import") (part "R-US_R0603"))
    )
    (comp (ref "R49")
      (value "1.0k")
      (footprint "eagle-import:R0603")
      (libsource (lib "eagle-import") (part "R-US_R0603"))
    )
    (comp (ref "R64")
      (value "1.0k")
      (footprint "eagle-import:R0402")
      (libsource (lib "eagle-import") (part "R-US_R0402"))
    )
    (comp (ref "R65")
      (value "1.0k")
      (footprint "eagle-import:R0402")
      (libsource (lib "eagle-import") (part "R-US_R0402"))
    )
    (comp (ref "R66")
      (value "1.0k")
      (footprint "eagle-import:R0402")
      (libsource (lib "eagle-import") (part "R-US_R0402"))
    )
    (comp (ref "R67")
      (value "1.0k")
      (footprint "eagle-import:R0402")
      (libsource (lib "eagle-import") (part "R-US_R0402"))
    )
  )
  (nets
    (net (code "1") (name "+3V3") (class "Default")
      (node (ref "C1") (pin "1") (pinfunction "1_1") (pintype "passive"))
      (node (ref "C10") (pin "+") (pinfunction "+_+") (pintype "passive"))
      (node (ref "C15") (pin "1") (pinfunction "1_1") (pintype "passive"))
      (node (ref "C16") (pin "1") (pinfunction "1_1") (pintype "passive"))
      (node (ref "C3") (pin "1") (pinfunction "1_1") (pintype "passive"))
      (node (ref "C6") (pin "1") (pinfunction "1_1") (pintype "passive"))
      (node (ref "C7") (pin "1") (pinfunction "1_1") (pintype "passive"))
      (node (ref "IC1") (pin "1") (pinfunction "VBAT_1") (pintype "power_in"))
      (node (ref "IC1") (pin "17") (pinfunction "VDD_2_17") (pintype "power_in"))
      (node (ref "IC1") (pin "48") (pinfunction "VDD_1_48") (pintype "power_in"))
      (node (ref "IC3") (pin "3") (pinfunction "VO_3") (pintype "passive"))
      (node (ref "IC4") (pin "12") (pinfunction "DVDD_12") (pintype "power_in"))
      (node (ref "R3") (pin "1") (pinfunction "1_1") (pintype "passive"))
    )
    (net (code "2") (name "+3V3_A") (class "Default")
      (node (ref "C12") (pin "1") (pinfunction "1_1") (pintype "passive"))
      (node (ref "C13") (pin "1") (pinfunction "1_1") (pintype "passive"))
      (node (ref "C14") (pin "1") (pinfunction "1_1") (pintype "passive"))
      (node (ref "C17") (pin "1") (pinfunction "1_1") (pintype "passive"))
      (node (ref "C29") (pin "+") (pinfunction "+_+") (pintype "passive"))
      (node (ref "C30") (pin "1") (pinfunction "1_1") (pintype "passive"))
      (node (ref "C43") (pin "1") (pinfunction "1_1") (pintype "passive"))
      (node (ref "C5") (pin "1") (pinfunction "1_1") (pintype "passive"))
      (node (ref "C50") (pin "+") (pinfunction "+_+") (pintype "passive"))
      (node (ref "C8") (pin "1") (pinfunction "1_1") (pintype "passive"))
      (node (ref "C9") (pin "+") (pinfunction "+_+") (pintype "passive"))
      (node (ref "D2") (pin "2") (pinfunction "C_2") (pintype "passive"))
      (node (ref "IC1") (pin "24") (pinfunction "VDDSD_24") (pintype "power_in"))
      (node (ref "IC1") (pin "25") (pinfunction "VREFSD+_25") (pintype "power_in"))
      (node (ref "IC1") (pin "9") (pinfunction "VDDA_9") (pintype "power_in"))
      (node (ref "IC2") (pin "16") (pinfunction "VCC_16") (pintype "power_in"))
      (node (ref "IC4") (pin "4") (pinfunction "AVDD_4") (pintype "power_in"))
      (node (ref "IC5") (pin "1") (pinfunction "VO_1") (pintype "passive"))
      (node (ref "IC6") (pin "4") (pinfunction "V+_4") (pintype "power_in"))
      (node (ref "IC7") (pin "4") (pinfunction "V+_4") (pintype "power_in"))
      (node (ref "R11") (pin "P$1") (pinfunction "E_P$1") (pintype "passive"))
      (node (ref "R12") (pin "P$1") (pinfunction "E_P$1") (pintype "passive"))
      (node (ref "R22") (pin "P$1") (pinfunction "E_P$1") (pintype "passive"))
      (node (ref "R23") (pin "P$1") (pinfunction "E_P$1") (pintype "passive"))
      (node (ref "R24") (pin "P$1") (pinfunction "E_P$1") (pintype "passive"))
      (node (ref "R56") (pin "P$1") (pinfunction "E_P$1") (pintype "passive"))
      (node (ref "R57") (pin "P$1") (pinfunction "E_P$1") (pintype "passive"))
      (node (ref "R58") (pin "P$1") (pinfunction "E_P$1") (pintype "passive"))
      (node (ref "R59") (pin "P$1") (pinfunction "E_P$1") (pintype "passive"))
      (node (ref "R60") (pin "P$1") (pinfunction "E_P$1") (pintype "passive"))
    )
    (net (code "3") (name "ADC_CLOCK") (class "Default")
      (node (ref "C36") (pin "2") (pinfunction "2_2") (pintype "passive"))
      (node (ref "IC1") (pin "20") (pinfunction "PB2/SDADC1_AIN4P/SDADC2_AIN6P_20") (pintype "bidirectional"))
      (node (ref "IC7") (pin "1") (pinfunction "OUT_1") (pintype "output"))
      (node (ref "R37") (pin "1") (pinfunction "1_1") (pintype "passive"))
    )
    (net (code "4") (name "ADC_FM") (class "Default")
      (node (ref "C46") (pin "2") (pinfunction "2_2") (pintype "passive"))
      (node (ref "IC1") (pin "21") (pinfunction "PE8/SDADC1_AIN8P/SDADC2_AIN8P_21") (pintype "bidirectional"))
      (node (ref "IC7") (pin "7") (pinfunction "OUT_7") (pintype "output"))
      (node (ref "R52") (pin "1") (pinfunction "1_1") (pintype "passive"))
    )
    (net (code "5") (name "ADC_SHAPE") (class "Default")
      (node (ref "C32") (pin "2") (pinfunction "2_2") (pintype "passive"))
      (node (ref "IC1") (pin "27") (pinfunction "PB15/SPI2_MOSI/I2S2_SD/SDADC3_AIN7P/SDADC3_AIN8M_27") (pintype "bidirectional"))
      (node (ref "IC6") (pin "8") (pinfunction "OUT_8") (pintype "output"))
      (node (ref "R27") (pin "1") (pinfunction "1_1") (pintype "passive"))
    )
    (net (code "6") (name "ADC_SHIFT") (class "Default")
      (node (ref "C28") (pin "2") (pinfunction "2_2") (pintype "passive"))
      (node (ref "IC1") (pin "28") (pinfunction "PD8/SPI2_SCK/I2S2_CK/USART3_TX/SDADC3_AIN6P_28") (pintype "bidirectional"))
      (node (ref "IC6") (pin "14") (pinfunction "OUT_14") (pintype "output"))
      (node (ref "R19") (pin "1") (pinfunction "1_1") (pintype "passive"))
    )
    (net (code "7") (name "ADC_SLOPE") (class "Default")
      (node (ref "C27") (pin "2") (pinfunction "2_2") (pintype "passive"))
      (node (ref "IC1") (pin "18") (pinfunction "PB0/SPI1_MOSI/I2S1_SD/TIM3_CH3/ADC_IN8/SDADC1_AIN6P_18") (pintype "bidirectional"))
      (node (ref "IC6") (pin "1") (pinfunction "OUT_1") (pintype "output"))
      (node (ref "R18") (pin "1") (pinfunction "1_1") (pintype "passive"))
    )
    (net (code "8") (name "ADC_SMOOTHNESS") (class "Default")
      (node (ref "C41") (pin "2") (pinfunction "2_2") (pintype "passive"))
      (node (ref "IC1") (pin "26") (pinfunction "PB14/SPI2_MISO/I2S2_MCK/USART3_RTS/SDADC3_AIN8P_26") (pintype "bidirectional"))
      (node (ref "IC7") (pin "14") (pinfunction "OUT_14") (pintype "output"))
      (node (ref "R41") (pin "1") (pinfunction "1_1") (pintype "passive"))
    )
    (net (code "9") (name "ADC_TRIG") (class "Default")
      (node (ref "C31") (pin "2") (pinfunction "2_2") (pintype "passive"))
      (node (ref "IC1") (pin "19") (pinfunction "PB1/TIM3_CH4/ADC_IN9/SDADC1_AIN5P/SDADC1_AIN6M_19") (pintype "bidirectional"))
      (node (ref "IC6") (pin "7") (pinfunction "OUT_7") (pintype "output"))
      (node (ref "R28") (pin "1") (pinfunction "1_1") (pintype "passive"))
    )
    (net (code "10") (name "ADC_V_OCT") (class "Default")
      (node (ref "C47") (pin "2") (pinfunction "2_2") (pintype "passive"))
      (node (ref "IC1") (pin "22") (pinfunction "PE9/SDADC1_AIN7P/SDADC1_AIN8M/SDADC2_AIN7P/SDADC2_AIN8M_22") (pintype "bidirectional"))
      (node (ref "IC7") (pin "8") (pinfunction "OUT_8") (pintype "output"))
      (node (ref "R53") (pin "1") (pinfunction "1_1") (pintype "passive"))
    )
    (net (code "11") (name "AREF_-10") (class "Default")
      (node (ref "C42") (pin "1") (pinfunction "1_1") (pintype "passive"))
      (node (ref "IC10") (pin "2") (pinfunction "A_2") (pintype "passive"))
      (node (ref "R20") (pin "2") (pinfunction "2_2") (pintype "passive"))
      (node (ref "R21") (pin "2") (pinfunction "2_2") (pintype "passive"))
      (node (ref "R25") (pin "2") (pinfunction "2_2") (pintype "passive"))
      (node (ref "R26") (pin "2") (pinfunction "2_2") (pintype "passive"))
      (node (ref "R43") (pin "2") (pinfunction "2_2") (pintype "passive"))
      (node (ref "R44") (pin "2") (pinfunction "2_2") (pintype "passive"))
      (node (ref "R46") (pin "2") (pinfunction "2_2") (pintype "passive"))
      (node (ref "R50") (pin "2") (pinfunction "2_2") (pintype "passive"))
      (node (ref "R51") (pin "2") (pinfunction "2_2") (pintype "passive"))
    )
    (net (code "12") (name "DAC_1") (class "Default")
      (node (ref "IC4") (pin "1") (pinfunction "OUTA_1") (pintype "output"))
      (node (ref "R31") (pin "2") (pinfunction "2_2") (pintype "passive"))
    )
    (net (code "13") (name "DAC_2") (class "Default")
      (node (ref "IC4") (pin "2") (pinfunction "OUTB_2") (pintype "output"))
      (node (ref "R32") (pin "2") (pinfunction "2_2") (pintype "passive"))
    )
    (net (code "14") (name "DAC_3") (class "Default")
      (node (ref "IC4") (pin "7") (pinfunction "OUTC_7") (pintype "output"))
      (node (ref "R33") (pin "2") (pinfunction "2_2") (pintype "passive"))
    )
    (net (code "15") (name "DAC_4") (class "Default")
      (node (ref "IC4") (pin "8") (pinfunction "OUTD_8") (pintype "output"))
      (node (ref "R34") (pin "2") (pinfunction "2_2") (pintype "passive"))
    )
    (net (code "16") (name "DAC_MOSI") (class "Default")
      (node (ref "IC1") (pin "31") (pinfunction "PA10/SPI2_MOSI/I2S2_SD/I2C2_SDA/USART1_RX/TIM2_CH4_31") (pintype "bidirectional"))
      (node (ref "IC4") (pin "11") (pinfunction "IN_11") (pintype "input"))
    )
    (net (code "17") (name "DAC_SCK") (class "Default")
      (node (ref "IC1") (pin "29") (pinfunction "PA8/SPI2_SCK/I2S2_CK/I2C2_SMBA/USART1_CK/TIM5_CH1_29") (pintype "bidirectional"))
      (node (ref "IC4") (pin "10") (pinfunction "SCK_10") (pintype "input"))
    )
    (net (code "18") (name "DAC_SS") (class "Default")
      (node (ref "IC1") (pin "32") (pinfunction "PA11/SPI2_NSS/I2S2_WS/SPI1_NSS/I2S1_WS/USART1_CTS/CAN_RX/TIM4_CH1/TIM5_CH2_32") (pintype "bidirectional"))
      (node (ref "IC4") (pin "9") (pinfunction "SYNC_9") (pintype "input"))
    )
    (net (code "19") (name "FREQUENCY_ATT") (class "Default")
      (node (ref "C52") (pin "1") (pinfunction "1_1") (pintype "passive"))
      (node (ref "IC2") (pin "2") (pinfunction "X6_2") (pintype "bidirectional"))
      (node (ref "R57") (pin "P$2") (pinfunction "S_P$2") (pintype "passive"))
    )
    (net (code "20") (name "FREQUENCY_POT") (class "Default")
      (node (ref "C22") (pin "1") (pinfunction "1_1") (pintype "passive"))
      (node (ref "IC1") (pin "16") (pinfunction "PA6/SPI1_MISO/I2S1_MCK/TIM3_CH1/ADC_IN6/DAC2_OUT1_16") (pintype "bidirectional"))
      (node (ref "R11") (pin "P$2") (pinfunction "S_P$2") (pintype "passive"))
    )
    (net (code "21") (name "GND") (class "Default")
      (node (ref "C1") (pin "2") (pinfunction "2_2") (pintype "passive"))
      (node (ref "C10") (pin "-") (pinfunction "-_-") (pintype "passive"))
      (node (ref "C11") (pin "1") (pinfunction "1_1") (pintype "passive"))
      (node (ref "C12") (pin "2") (pinfunction "2_2") (pintype "passive"))
      (node (ref "C13") (pin "2") (pinfunction "2_2") (pintype "passive"))
      (node (ref "C14") (pin "2") (pinfunction "2_2") (pintype "passive"))
      (node (ref "C15") (pin "2") (pinfunction "2_2") (pintype "passive"))
      (node (ref "C16") (pin "2") (pinfunction "2_2") (pintype "passive"))
      (node (ref "C17") (pin "2") (pinfunction "2_2") (pintype "passive"))
      (node (ref "C18") (pin "2") (pinfunction "2_2") (pintype "passive"))
      (node (ref "C19") (pin "2") (pinfunction "2_2") (pintype "passive"))
      (node (ref "C2") (pin "2") (pinfunction "2_2") (pintype "passive"))
      (node (ref "C20") (pin "2") (pinfunction "2_2") (pintype "passive"))
      (node (ref "C21") (pin "2") (pinfunction "2_2") (pintype "passive"))
      (node (ref "C22") (pin "2") (pinfunction "2_2") (pintype "passive"))
      (node (ref "C23") (pin "2") (pinfunction "2_2") (pintype "passive"))
      (node (ref "C24") (pin "-") (pinfunction "-_-") (pintype "passive"))
      (node (ref "C25") (pin "2") (pinfunction "2_2") (pintype "passive"))
      (node (ref "C26") (pin "+") (pinfunction "+_+") (pintype "passive"))
      (node (ref "C29") (pin "-") (pinfunction "-_-") (pintype "passive"))
      (node (ref "C3") (pin "2") (pinfunction "2_2") (pintype "passive"))
      (node (ref "C30") (pin "2") (pinfunction "2_2") (pintype "passive"))
      (node (ref "C33") (pin "1") (pinfunction "1_1") (pintype "passive"))
      (node (ref "C34") (pin "1") (pinfunction "1_1") (pintype "passive"))
      (node (ref "C35") (pin "2") (pinfunction "2_2") (pintype "passive"))
      (node (ref "C4") (pin "1") (pinfunction "1_1") (pintype "passive"))
      (node (ref "C42") (pin "2") (pinfunction "2_2") (pintype "passive"))
      (node (ref "C43") (pin "2") (pinfunction "2_2") (pintype "passive"))
      (node (ref "C44") (pin "2") (pinfunction "2_2") (pintype "passive"))
      (node (ref "C45") (pin "2") (pinfunction "2_2") (pintype "passive"))
      (node (ref "C48") (pin "2") (pinfunction "2_2") (pintype "passive"))
      (node (ref "C49") (pin "2") (pinfunction "2_2") (pintype "passive"))
      (node (ref "C5") (pin "2") (pinfunction "2_2") (pintype "passive"))
      (node (ref "C50") (pin "-") (pinfunction "-_-") (pintype "passive"))
      (node (ref "C51") (pin "2") (pinfunction "2_2") (pintype "passive"))
      (node (ref "C52") (pin "2") (pinfunction "2_2") (pintype "passive"))
      (node (ref "C53") (pin "2") (pinfunction "2_2") (pintype "passive"))
      (node (ref "C54") (pin "2") (pinfunction "2_2") (pintype "passive"))
      (node (ref "C55") (pin "2") (pinfunction "2_2") (pintype "passive"))
      (node (ref "C56") (pin "2") (pinfunction "2_2") (pintype "passive"))
      (node (ref "C6") (pin "2") (pinfunction "2_2") (pintype "passive"))
      (node (ref "C7") (pin "2") (pinfunction "2_2") (pintype "passive"))
      (node (ref "C8") (pin "2") (pinfunction "2_2") (pintype "passive"))
      (node (ref "C9") (pin "-") (pinfunction "-_-") (pintype "passive"))
      (node (ref "D10") (pin "1") (pinfunction "A_1") (pintype "passive"))
      (node (ref "D11") (pin "1") (pinfunction "A_1") (pintype "passive"))
      (node (ref "D2") (pin "1") (pinfunction "A_1") (pintype "passive"))
      (node (ref "D4") (pin "1") (pinfunction "A_1") (pintype "passive"))
      (node (ref "D5") (pin "1") (pinfunction "A_1") (pintype "passive"))
      (node (ref "D6") (pin "1") (pinfunction "A_1") (pintype "passive"))
      (node (ref "D7") (pin "1") (pinfunction "A_1") (pintype "passive"))
      (node (ref "D8") (pin "1") (pinfunction "A_1") (pintype "passive"))
      (node (ref "D9") (pin "1") (pinfunction "A_1") (pintype "passive"))
      (node (ref "IC1") (pin "23") (pinfunction "VSSSD/VREFSD-_23") (pintype "power_in"))
      (node (ref "IC1") (pin "44") (pinfunction "BOOT0_44") (pintype "bidirectional"))
      (node (ref "IC1") (pin "47") (pinfunction "VSS_1_47") (pintype "power_in"))
      (node (ref "IC1") (pin "8") (pinfunction "VSSA_8") (pintype "power_in"))
      (node (ref "IC10") (pin "1") (pinfunction "C_1") (pintype "passive"))
      (node (ref "IC2") (pin "6") (pinfunction "INH_6") (pintype "input"))
      (node (ref "IC2") (pin "7") (pinfunction "VEE_7") (pintype "power_in"))
      (node (ref "IC2") (pin "8") (pinfunction "GND_8") (pintype "power_in"))
      (node (ref "IC3") (pin "2") (pinfunction "GND_2") (pintype "passive"))
      (node (ref "IC4") (pin "13") (pinfunction "A0_13") (pintype "input"))
      (node (ref "IC4") (pin "14") (pinfunction "A1_14") (pintype "input"))
      (node (ref "IC4") (pin "15") (pinfunction "ENABLE_15") (pintype "input"))
      (node (ref "IC4") (pin "16") (pinfunction "LDAC_16") (pintype "input"))
      (node (ref "IC4") (pin "5") (pinfunction "VREFL_5") (pintype "bidirectional"))
      (node (ref "IC4") (pin "6") (pinfunction "GND_6") (pintype "power_in"))
      (node (ref "IC5") (pin "2") (pinfunction "GND_2") (pintype "passive"))
      (node (ref "IC6") (pin "10") (pinfunction "+IN_10") (pintype "input"))
      (node (ref "IC6") (pin "11") (pinfunction "V-_11") (pintype "power_in"))
      (node (ref "IC6") (pin "12") (pinfunction "+IN_12") (pintype "input"))
      (node (ref "IC6") (pin "3") (pinfunction "+IN_3") (pintype "input"))
      (node (ref "IC6") (pin "5") (pinfunction "+IN_5") (pintype "input"))
      (node (ref "IC7") (pin "10") (pinfunction "+IN_10") (pintype "input"))
      (node (ref "IC7") (pin "11") (pinfunction "V-_11") (pintype "power_in"))
      (node (ref "IC7") (pin "12") (pinfunction "+IN_12") (pintype "input"))
      (node (ref "IC7") (pin "3") (pinfunction "+IN_3") (pintype "input"))
      (node (ref "IC7") (pin "5") (pinfunction "+IN_5") (pintype "input"))
      (node (ref "J1") (pin "P1") (pinfunction "1_P1") (pintype "passive"))
      (node (ref "J1") (pin "P2") (pinfunction "2_P2") (pintype "passive"))
      (node (ref "J10") (pin "P1") (pinfunction "1_P1") (pintype "passive"))
      (node (ref "J11") (pin "P1") (pinfunction "1_P1") (pintype "passive"))
      (node (ref "J12") (pin "P1") (pinfunction "1_P1") (pintype "passive"))
      (node (ref "J2") (pin "P1") (pinfunction "1_P1") (pintype "passive"))
      (node (ref "J3") (pin "P1") (pinfunction "1_P1") (pintype "passive"))
      (node (ref "J3") (pin "P2") (pinfunction "2_P2") (pintype "passive"))
      (node (ref "J4") (pin "P1") (pinfunction "1_P1") (pintype "passive"))
      (node (ref "J4") (pin "P2") (pinfunction "2_P2") (pintype "passive"))
      (node (ref "J5") (pin "P1") (pinfunction "1_P1") (pintype "passive"))
      (node (ref "J5") (pin "P2") (pinfunction "2_P2") (pintype "passive"))
      (node (ref "J6") (pin "P1") (pinfunction "1_P1") (pintype "passive"))
      (node (ref "J6") (pin "P2") (pinfunction "2_P2") (pintype "passive"))
      (node (ref "J7") (pin "P1") (pinfunction "1_P1") (pintype "passive"))
      (node (ref "J8") (pin "P1") (pinfunction "1_P1") (pintype "passive"))
      (node (ref "J9") (pin "P1") (pinfunction "1_P1") (pintype "passive"))
      (node (ref "JP5") (pin "3") (pinfunction "3_3") (pintype "passive"))
      (node (ref "JP5") (pin "4") (pinfunction "4_4") (pintype "passive"))
      (node (ref "JP5") (pin "5") (pinfunction "5_5") (pintype "passive"))
      (node (ref "JP5") (pin "6") (pinfunction "6_6") (pintype "passive"))
      (node (ref "JP5") (pin "7") (pinfunction "7_7") (pintype "passive"))
      (node (ref "JP5") (pin "8") (pinfunction "8_8") (pintype "passive"))
      (node (ref "JP6") (pin "1") (pinfunction "1_1") (pintype "passive"))
      (node (ref "LED1") (pin "2") (pinfunction "C_2") (pintype "bidirectional"))
      (node (ref "LED2") (pin "2") (pinfunction "C_2") (pintype "bidirectional"))
      (node (ref "LED3") (pin "2") (pinfunction "C_2") (pintype "bidirectional"))
      (node (ref "Q1") (pin "2") (pinfunction "LID1_2") (pintype "power_in"))
      (node (ref "Q1") (pin "4") (pinfunction "LID2_4") (pintype "power_in"))
      (node (ref "R11") (pin "P$3") (pinfunction "A_P$3") (pintype "passive"))
      (node (ref "R12") (pin "P$3") (pinfunction "A_P$3") (pintype "passive"))
      (node (ref "R15") (pin "1") (pinfunction "1_1") (pintype "passive"))
      (node (ref "R22") (pin "P$3") (pinfunction "A_P$3") (pintype "passive"))
      (node (ref "R23") (pin "P$3") (pinfunction "A_P$3") (pintype "passive"))
      (node (ref "R24") (pin "P$3") (pinfunction "A_P$3") (pintype "passive"))
      (node (ref "R56") (pin "P$3") (pinfunction "A_P$3") (pintype "passive"))
      (node (ref "R57") (pin "P$3") (pinfunction "A_P$3") (pintype "passive"))
      (node (ref "R58") (pin "P$3") (pinfunction "A_P$3") (pintype "passive"))
      (node (ref "R59") (pin "P$3") (pinfunction "A_P$3") (pintype "passive"))
      (node (ref "R60") (pin "P$3") (pinfunction "A_P$3") (pintype "passive"))
      (node (ref "R64") (pin "2") (pinfunction "2_2") (pintype "passive"))
      (node (ref "R65") (pin "2") (pinfunction "2_2") (pintype "passive"))
      (node (ref "R66") (pin "2") (pinfunction "2_2") (pintype "passive"))
      (node (ref "R67") (pin "2") (pinfunction "2_2") (pintype "passive"))
      (node (ref "SW1") (pin "1") (pinfunction "1_1") (pintype "passive"))
      (node (ref "SW1") (pin "2") (pinfunction "2_2") (pintype "passive"))
      (node (ref "SW2") (pin "1") (pinfunction "1_1") (pintype "passive"))
      (node (ref "SW2") (pin "2") (pinfunction "2_2") (pintype "passive"))
      (node (ref "SW3") (pin "1") (pinfunction "1_1") (pintype "passive"))
      (node (ref "SW3") (pin "2") (pinfunction "2_2") (pintype "passive"))
    )
    (net (code "22") (name "LED_MODE_G") (class "Default")
      (node (ref "IC1") (pin "35") (pinfunction "PF6/SPI1_MOSI/I2S1_SD/USART3_RTS/TIM4_CH4/I2C2_SCL_35") (pintype "bidirectional"))
      (node (ref "R10") (pin "1") (pinfunction "1_1") (pintype "passive"))
    )
    (net (code "23") (name "LED_MODE_R") (class "Default")
      (node (ref "IC1") (pin "36") (pinfunction "PF7/I2C2_SDA/USART2_CK_36") (pintype "bidirectional"))
      (node (ref "R13") (pin "1") (pinfunction "1_1") (pintype "passive"))
    )
    (net (code "24") (name "LED_RANGE_G") (class "Default")
      (node (ref "IC1") (pin "42") (pinfunction "PB6/I2C1_SCL/USART1_TX/TIM4_CH1_42") (pintype "bidirectional"))
      (node (ref "R6") (pin "1") (pinfunction "1_1") (pintype "passive"))
    )
    (net (code "25") (name "LED_RANGE_R") (class "Default")
      (node (ref "IC1") (pin "41") (pinfunction "PB5/SPI1_MOSI/I2S1_SD/SPI3_MOSI/I2S3_SD/I2C1_SMBAI/USART2_CK/TIM3_CH2_41") (pintype "bidirectional"))
      (node (ref "R1") (pin "1") (pinfunction "1_1") (pintype "passive"))
    )
    (net (code "26") (name "LED_SHIFT_G") (class "Default")
      (node (ref "IC1") (pin "40") (pinfunction "PB4/SPI1_MISO/I2S1_MCK/SPI3_MISO/I2S3_MCK/USART2_RX/TIM3_CH1/NJTRST_40") (pintype "bidirectional"))
      (node (ref "R2") (pin "1") (pinfunction "1_1") (pintype "passive"))
    )
    (net (code "27") (name "LED_SHIFT_R") (class "Default")
      (node (ref "IC1") (pin "39") (pinfunction "PB3/SPI1_SCK/I2S1_CK/SPI3_SCK/I2S3_CK/USART2_TX/TIM2_CH2/JTDO/SPI3_SCK/JTDO_39") (pintype "bidirectional"))
      (node (ref "R7") (pin "1") (pinfunction "1_1") (pintype "passive"))
    )
    (net (code "28") (name "MUXED_POTS") (class "Default")
      (node (ref "C56") (pin "1") (pinfunction "1_1") (pintype "passive"))
      (node (ref "IC1") (pin "11") (pinfunction "PA1/SPI3_SCK/I2S3_CK/USART2_RTS/TIM2_CH2/TIM5_CH2/ADC_IN1_11") (pintype "bidirectional"))
      (node (ref "IC2") (pin "3") (pinfunction "X_3") (pintype "bidirectional"))
    )
    (net (code "29") (name "MUX_ADDR_0") (class "Default")
      (node (ref "IC1") (pin "13") (pinfunction "PA3/SPI3_MOSI/I2S3_SD/USART2_RX/TIM2_CH4/TIM5_CH4/ADC_IN3_13") (pintype "bidirectional"))
      (node (ref "IC2") (pin "11") (pinfunction "A_11") (pintype "input"))
    )
    (net (code "30") (name "MUX_ADDR_1") (class "Default")
      (node (ref "IC1") (pin "14") (pinfunction "PA4/SPI1_NSS/I2S1_WS/SPI3_NSS/I2S3_WS/USART2_CK/TIM3_CH2/ADC_IN4/DAC1_OUT1_14") (pintype "bidirectional"))
      (node (ref "IC2") (pin "10") (pinfunction "B_10") (pintype "input"))
    )
    (net (code "31") (name "MUX_ADDR_2") (class "Default")
      (node (ref "IC1") (pin "15") (pinfunction "PA5/SPI1_SCK/I2S1_CK/TIM2_CH1/ADC_IN5/DAC1_OUT2_15") (pintype "bidirectional"))
      (node (ref "IC2") (pin "9") (pinfunction "C_9") (pintype "input"))
    )
    (net (code "32") (name "NORMALIZATION_PROBE") (class "Default")
      (node (ref "D2") (pin "3") (pinfunction "AC_3") (pintype "passive"))
      (node (ref "IC1") (pin "30") (pinfunction "PA9/SPI_MISO/I2S2_MCK/I2C2_SCL/USART1_TX/TIM2_CH3_30") (pintype "bidirectional"))
      (node (ref "R61") (pin "2") (pinfunction "2_2") (pintype "passive"))
      (node (ref "R62") (pin "2") (pinfunction "2_2") (pintype "passive"))
      (node (ref "R63") (pin "2") (pinfunction "2_2") (pintype "passive"))
    )
    (net (code "33") (name "Net-(C11-Pad2)") (class "Default")
      (node (ref "C11") (pin "2") (pinfunction "2_2") (pintype "passive"))
      (node (ref "Q1") (pin "1") (pinfunction "1_1") (pintype "passive"))
      (node (ref "R9") (pin "2") (pinfunction "2_2") (pintype "passive"))
    )
    (net (code "34") (name "Net-(C20-Pad1)") (class "Default")
      (node (ref "C20") (pin "1") (pinfunction "1_1") (pintype "passive"))
      (node (ref "D1") (pin "C") (pinfunction "C_C") (pintype "passive"))
      (node (ref "L1") (pin "1") (pinfunction "1_1") (pintype "passive"))
      (node (ref "L2") (pin "2") (pinfunction "2_2") (pintype "passive"))
      (node (ref "L3") (pin "2") (pinfunction "2_2") (pintype "passive"))
    )
    (net (code "35") (name "Net-(D1-PadA)") (class "Default")
      (node (ref "D1") (pin "A") (pinfunction "A_A") (pintype "passive"))
      (node (ref "JP5") (pin "10") (pinfunction "10_10") (pintype "passive"))
      (node (ref "JP5") (pin "9") (pinfunction "9_9") (pintype "passive"))
    )
    (net (code "36") (name "Net-(D3-PadA)") (class "Default")
      (node (ref "D3") (pin "A") (pinfunction "A_A") (pintype "passive"))
      (node (ref "L4") (pin "2") (pinfunction "2_2") (pintype "passive"))
    )
    (net (code "37") (name "Net-(D3-PadC)") (class "Default")
      (node (ref "D3") (pin "C") (pinfunction "C_C") (pintype "passive"))
      (node (ref "JP5") (pin "1") (pinfunction "1_1") (pintype "passive"))
      (node (ref "JP5") (pin "2") (pinfunction "2_2") (pintype "passive"))
    )
    (net (code "38") (name "Net-(D4-C)") (class "Default")
      (node (ref "D4") (pin "2") (pinfunction "C_2") (pintype "passive"))
      (node (ref "J5") (pin "P3") (pinfunction "3_P3") (pintype "passive"))
      (node (ref "R30") (pin "2") (pinfunction "2_2") (pintype "passive"))
    )
    (net (code "39") (name "Net-(D5-C)") (class "Default")
      (node (ref "D5") (pin "2") (pinfunction "C_2") (pintype "passive"))
      (node (ref "J6") (pin "P3") (pinfunction "3_P3") (pintype "passive"))
      (node (ref "R17") (pin "2") (pinfunction "2_2") (pintype "passive"))
    )
    (net (code "40") (name "Net-(D6-C)") (class "Default")
      (node (ref "D6") (pin "2") (pinfunction "C_2") (pintype "passive"))
      (node (ref "J4") (pin "P3") (pinfunction "3_P3") (pintype "passive"))
      (node (ref "R36") (pin "2") (pinfunction "2_2") (pintype "passive"))
    )
    (net (code "41") (name "Net-(D7-C)") (class "Default")
      (node (ref "D7") (pin "2") (pinfunction "C_2") (pintype "passive"))
      (node (ref "J3") (pin "P3") (pinfunction "3_P3") (pintype "passive"))
      (node (ref "R54") (pin "2") (pinfunction "2_2") (pintype "passive"))
    )
    (net (code "42") (name "Net-(D8-C)") (class "Default")
      (node (ref "D8") (pin "2") (pinfunction "C_2") (pintype "passive"))
      (node (ref "J1") (pin "P3") (pinfunction "3_P3") (pintype "passive"))
      (node (ref "R16") (pin "2") (pinfunction "2_2") (pintype "passive"))
    )
    (net (code "43") (name "Net-(D9-C)") (class "Default")
      (node (ref "D9") (pin "2") (pinfunction "C_2") (pintype "passive"))
      (node (ref "J2") (pin "P3") (pinfunction "3_P3") (pintype "passive"))
      (node (ref "R55") (pin "2") (pinfunction "2_2") (pintype "passive"))
    )
    (net (code "44") (name "Net-(D10-C)") (class "Default")
      (node (ref "D10") (pin "2") (pinfunction "C_2") (pintype "passive"))
      (node (ref "J7") (pin "P3") (pinfunction "3_P3") (pintype "passive"))
      (node (ref "R29") (pin "2") (pinfunction "2_2") (pintype "passive"))
    )
    (net (code "45") (name "Net-(D11-C)") (class "Default")
      (node (ref "D11") (pin "2") (pinfunction "C_2") (pintype "passive"))
      (node (ref "J8") (pin "P3") (pinfunction "3_P3") (pintype "passive"))
      (node (ref "R35") (pin "2") (pinfunction "2_2") (pintype "passive"))
    )
    (net (code "46") (name "Net-(IC1-PF0{slash}OSC_IN{slash}I2C2_SDA)") (class "Default")
      (node (ref "IC1") (pin "5") (pinfunction "PF0/OSC_IN/I2C2_SDA_5") (pintype "bidirectional"))
      (node (ref "R8") (pin "1") (pinfunction "1_1") (pintype "passive"))
    )
    (net (code "47") (name "Net-(IC1-PF1{slash}OSC_OUT{slash}I2C2_SCL)") (class "Default")
      (node (ref "IC1") (pin "6") (pinfunction "PF1/OSC_OUT/I2C2_SCL_6") (pintype "bidirectional"))
      (node (ref "R9") (pin "1") (pinfunction "1_1") (pintype "passive"))
    )
    (net (code "48") (name "Net-(IC3-VI)") (class "Default")
      (node (ref "C19") (pin "1") (pinfunction "1_1") (pintype "passive"))
      (node (ref "IC3") (pin "1") (pinfunction "VI_1") (pintype "input"))
      (node (ref "L1") (pin "2") (pinfunction "2_2") (pintype "passive"))
    )
    (net (code "49") (name "Net-(IC5-VI)") (class "Default")
      (node (ref "C25") (pin "1") (pinfunction "1_1") (pintype "passive"))
      (node (ref "IC5") (pin "3") (pinfunction "VI_3") (pintype "input"))
      (node (ref "L3") (pin "1") (pinfunction "1_1") (pintype "passive"))
    )
    (net (code "50") (name "Net-(IC6A--IN)") (class "Default")
      (node (ref "C27") (pin "1") (pinfunction "1_1") (pintype "passive"))
      (node (ref "IC6") (pin "2") (pinfunction "-IN_2") (pintype "input"))
      (node (ref "R16") (pin "1") (pinfunction "1_1") (pintype "passive"))
      (node (ref "R18") (pin "2") (pinfunction "2_2") (pintype "passive"))
      (node (ref "R20") (pin "1") (pinfunction "1_1") (pintype "passive"))
    )
    (net (code "51") (name "Net-(IC6B--IN)") (class "Default")
      (node (ref "C31") (pin "1") (pinfunction "1_1") (pintype "passive"))
      (node (ref "IC6") (pin "6") (pinfunction "-IN_6") (pintype "input"))
      (node (ref "R26") (pin "1") (pinfunction "1_1") (pintype "passive"))
      (node (ref "R28") (pin "2") (pinfunction "2_2") (pintype "passive"))
      (node (ref "R29") (pin "1") (pinfunction "1_1") (pintype "passive"))
    )
    (net (code "52") (name "Net-(IC6C--IN)") (class "Default")
      (node (ref "C32") (pin "1") (pinfunction "1_1") (pintype "passive"))
      (node (ref "IC6") (pin "9") (pinfunction "-IN_9") (pintype "input"))
      (node (ref "R25") (pin "1") (pinfunction "1_1") (pintype "passive"))
      (node (ref "R27") (pin "2") (pinfunction "2_2") (pintype "passive"))
      (node (ref "R30") (pin "1") (pinfunction "1_1") (pintype "passive"))
    )
    (net (code "53") (name "Net-(IC6D--IN)") (class "Default")
      (node (ref "C28") (pin "1") (pinfunction "1_1") (pintype "passive"))
      (node (ref "IC6") (pin "13") (pinfunction "-IN_13") (pintype "input"))
      (node (ref "R17") (pin "1") (pinfunction "1_1") (pintype "passive"))
      (node (ref "R19") (pin "2") (pinfunction "2_2") (pintype "passive"))
      (node (ref "R21") (pin "1") (pinfunction "1_1") (pintype "passive"))
    )
    (net (code "54") (name "Net-(IC7A--IN)") (class "Default")
      (node (ref "C36") (pin "1") (pinfunction "1_1") (pintype "passive"))
      (node (ref "IC7") (pin "2") (pinfunction "-IN_2") (pintype "input"))
      (node (ref "R35") (pin "1") (pinfunction "1_1") (pintype "passive"))
      (node (ref "R37") (pin "2") (pinfunction "2_2") (pintype "passive"))
      (node (ref "R44") (pin "1") (pinfunction "1_1") (pintype "passive"))
    )
    (net (code "55") (name "Net-(IC7B--IN)") (class "Default")
      (node (ref "C46") (pin "1") (pinfunction "1_1") (pintype "passive"))
      (node (ref "IC7") (pin "6") (pinfunction "-IN_6") (pintype "input"))
      (node (ref "R51") (pin "1") (pinfunction "1_1") (pintype "passive"))
      (node (ref "R52") (pin "2") (pinfunction "2_2") (pintype "passive"))
      (node (ref "R55") (pin "1") (pinfunction "1_1") (pintype "passive"))
    )
    (net (code "56") (name "Net-(IC7C--IN)") (class "Default")
      (node (ref "C47") (pin "1") (pinfunction "1_1") (pintype "passive"))
      (node (ref "IC7") (pin "9") (pinfunction "-IN_9") (pintype "input"))
      (node (ref "R50") (pin "1") (pinfunction "1_1") (pintype "passive"))
      (node (ref "R53") (pin "2") (pinfunction "2_2") (pintype "passive"))
      (node (ref "R54") (pin "1") (pinfunction "1_1") (pintype "passive"))
    )
    (net (code "57") (name "Net-(IC7D--IN)") (class "Default")
      (node (ref "C41") (pin "1") (pinfunction "1_1") (pintype "passive"))
      (node (ref "IC7") (pin "13") (pinfunction "-IN_13") (pintype "input"))
      (node (ref "R36") (pin "1") (pinfunction "1_1") (pintype "passive"))
      (node (ref "R41") (pin "2") (pinfunction "2_2") (pintype "passive"))
      (node (ref "R43") (pin "1") (pinfunction "1_1") (pintype "passive"))
    )
    (net (code "58") (name "Net-(IC8A-+IN)") (class "Default")
      (node (ref "C39") (pin "2") (pinfunction "2_2") (pintype "passive"))
      (node (ref "IC8") (pin "14") (pinfunction "OUT_14") (pintype "output"))
      (node (ref "IC8") (pin "3") (pinfunction "+IN_3") (pintype "input"))
      (node (ref "R48") (pin "2") (pinfunction "2_2") (pintype "passive"))
    )
    (net (code "59") (name "Net-(IC8A--IN)") (class "Default")
      (node (ref "IC8") (pin "2") (pinfunction "-IN_2") (pintype "input"))
      (node (ref "LED6") (pin "2") (pinfunction "2_2") (pintype "bidirectional"))
      (node (ref "R66") (pin "1") (pinfunction "1_1") (pintype "passive"))
    )
    (net (code "60") (name "Net-(IC8A-OUT)") (class "Default")
      (node (ref "IC8") (pin "1") (pinfunction "OUT_1") (pintype "output"))
      (node (ref "LED6") (pin "1") (pinfunction "1_1") (pintype "bidirectional"))
    )
    (net (code "61") (name "Net-(IC8B-+IN)") (class "Default")
      (node (ref "C40") (pin "2") (pinfunction "2_2") (pintype "passive"))
      (node (ref "IC8") (pin "5") (pinfunction "+IN_5") (pintype "input"))
      (node (ref "IC8") (pin "8") (pinfunction "OUT_8") (pintype "output"))
      (node (ref "R49") (pin "2") (pinfunction "2_2") (pintype "passive"))
    )
    (net (code "62") (name "Net-(IC8B--IN)") (class "Default")
      (node (ref "IC8") (pin "6") (pinfunction "-IN_6") (pintype "input"))
      (node (ref "LED7") (pin "2") (pinfunction "2_2") (pintype "bidirectional"))
      (node (ref "R67") (pin "1") (pinfunction "1_1") (pintype "passive"))
    )
    (net (code "63") (name "Net-(IC8B-OUT)") (class "Default")
      (node (ref "IC8") (pin "7") (pinfunction "OUT_7") (pintype "output"))
      (node (ref "LED7") (pin "1") (pinfunction "1_1") (pintype "bidirectional"))
    )
    (net (code "64") (name "Net-(IC8C--IN)") (class "Default")
      (node (ref "C40") (pin "1") (pinfunction "1_1") (pintype "passive"))
      (node (ref "IC8") (pin "9") (pinfunction "-IN_9") (pintype "input"))
      (node (ref "R34") (pin "1") (pinfunction "1_1") (pintype "passive"))
      (node (ref "R40") (pin "2") (pinfunction "2_2") (pintype "passive"))
    )
    (net (code "65") (name "Net-(IC8D--IN)") (class "Default")
      (node (ref "C39") (pin "1") (pinfunction "1_1") (pintype "passive"))
      (node (ref "IC8") (pin "13") (pinfunction "-IN_13") (pintype "input"))
      (node (ref "R33") (pin "1") (pinfunction "1_1") (pintype "passive"))
      (node (ref "R39") (pin "2") (pinfunction "2_2") (pintype "passive"))
    )
    (net (code "66") (name "Net-(IC9A-+IN)") (class "Default")
      (node (ref "C37") (pin "2") (pinfunction "2_2") (pintype "passive"))
      (node (ref "IC9") (pin "14") (pinfunction "OUT_14") (pintype "output"))
      (node (ref "IC9") (pin "3") (pinfunction "+IN_3") (pintype "input"))
      (node (ref "R47") (pin "2") (pinfunction "2_2") (pintype "passive"))
    )
    (net (code "67") (name "Net-(IC9A--IN)") (class "Default")
      (node (ref "IC9") (pin "2") (pinfunction "-IN_2") (pintype "input"))
      (node (ref "LED4") (pin "2") (pinfunction "2_2") (pintype "bidirectional"))
      (node (ref "R64") (pin "1") (pinfunction "1_1") (pintype "passive"))
    )
    (net (code "68") (name "Net-(IC9A-OUT)") (class "Default")
      (node (ref "IC9") (pin "1") (pinfunction "OUT_1") (pintype "output"))
      (node (ref "LED4") (pin "1") (pinfunction "1_1") (pintype "bidirectional"))
    )
    (net (code "69") (name "Net-(IC9B-+IN)") (class "Default")
      (node (ref "C38") (pin "2") (pinfunction "2_2") (pintype "passive"))
      (node (ref "IC9") (pin "5") (pinfunction "+IN_5") (pintype "input"))
      (node (ref "IC9") (pin "8") (pinfunction "OUT_8") (pintype "output"))
      (node (ref "R45") (pin "2") (pinfunction "2_2") (pintype "passive"))
    )
    (net (code "70") (name "Net-(IC9B--IN)") (class "Default")
      (node (ref "IC9") (pin "6") (pinfunction "-IN_6") (pintype "input"))
      (node (ref "LED5") (pin "2") (pinfunction "2_2") (pintype "bidirectional"))
      (node (ref "R65") (pin "1") (pinfunction "1_1") (pintype "passive"))
    )
    (net (code "71") (name "Net-(IC9B-OUT)") (class "Default")
      (node (ref "IC9") (pin "7") (pinfunction "OUT_7") (pintype "output"))
      (node (ref "LED5") (pin "1") (pinfunction "1_1") (pintype "bidirectional"))
    )
    (net (code "72") (name "Net-(IC9C--IN)") (class "Default")
      (node (ref "C38") (pin "1") (pinfunction "1_1") (pintype "passive"))
      (node (ref "IC9") (pin "9") (pinfunction "-IN_9") (pintype "input"))
      (node (ref "R32") (pin "1") (pinfunction "1_1") (pintype "passive"))
      (node (ref "R38") (pin "2") (pinfunction "2_2") (pintype "passive"))
    )
    (net (code "73") (name "Net-(IC9D--IN)") (class "Default")
      (node (ref "C37") (pin "1") (pinfunction "1_1") (pintype "passive"))
      (node (ref "IC9") (pin "13") (pinfunction "-IN_13") (pintype "input"))
      (node (ref "R31") (pin "1") (pinfunction "1_1") (pintype "passive"))
      (node (ref "R42") (pin "2") (pinfunction "2_2") (pintype "passive"))
    )
    (net (code "74") (name "Net-(J2-2)") (class "Default")
      (node (ref "J2") (pin "P2") (pinfunction "2_P2") (pintype "passive"))
      (node (ref "R61") (pin "1") (pinfunction "1_1") (pintype "passive"))
    )
    (net (code "75") (name "Net-(J7-2)") (class "Default")
      (node (ref "J7") (pin "P2") (pinfunction "2_P2") (pintype "passive"))
      (node (ref "R62") (pin "1") (pinfunction "1_1") (pintype "passive"))
    )
    (net (code "76") (name "Net-(J8-2)") (class "Default")
      (node (ref "J8") (pin "P2") (pinfunction "2_P2") (pintype "passive"))
      (node (ref "R63") (pin "1") (pinfunction "1_1") (pintype "passive"))
    )
    (net (code "77") (name "Net-(J9-3)") (class "Default")
      (node (ref "J9") (pin "P3") (pinfunction "3_P3") (pintype "passive"))
      (node (ref "R42") (pin "1") (pinfunction "1_1") (pintype "passive"))
      (node (ref "R47") (pin "1") (pinfunction "1_1") (pintype "passive"))
    )
    (net (code "78") (name "Net-(J10-3)") (class "Default")
      (node (ref "J10") (pin "P3") (pinfunction "3_P3") (pintype "passive"))
      (node (ref "R38") (pin "1") (pinfunction "1_1") (pintype "passive"))
      (node (ref "R45") (pin "1") (pinfunction "1_1") (pintype "passive"))
    )
    (net (code "79") (name "Net-(J11-3)") (class "Default")
      (node (ref "J11") (pin "P3") (pinfunction "3_P3") (pintype "passive"))
      (node (ref "R39") (pin "1") (pinfunction "1_1") (pintype "passive"))
      (node (ref "R48") (pin "1") (pinfunction "1_1") (pintype "passive"))
    )
    (net (code "80") (name "Net-(J12-3)") (class "Default")
      (node (ref "J12") (pin "P3") (pinfunction "3_P3") (pintype "passive"))
      (node (ref "R40") (pin "1") (pinfunction "1_1") (pintype "passive"))
      (node (ref "R49") (pin "1") (pinfunction "1_1") (pintype "passive"))
    )
    (net (code "81") (name "Net-(JP7-Pad1)") (class "Default")
      (node (ref "JP7") (pin "1") (pinfunction "1_1") (pintype "passive"))
      (node (ref "R4") (pin "1") (pinfunction "1_1") (pintype "passive"))
    )
    (net (code "82") (name "Net-(JP7-Pad2)") (class "Default")
      (node (ref "JP7") (pin "2") (pinfunction "2_2") (pintype "passive"))
      (node (ref "R5") (pin "1") (pinfunction "1_1") (pintype "passive"))
    )
    (net (code "83") (name "Net-(LED1-GRN)") (class "Default")
      (node (ref "LED1") (pin "1") (pinfunction "GRN_1") (pintype "bidirectional"))
      (node (ref "R6") (pin "2") (pinfunction "2_2") (pintype "passive"))
    )
    (net (code "84") (name "Net-(LED1-RED)") (class "Default")
      (node (ref "LED1") (pin "3") (pinfunction "RED_3") (pintype "bidirectional"))
      (node (ref "R1") (pin "2") (pinfunction "2_2") (pintype "passive"))
    )
    (net (code "85") (name "Net-(LED2-GRN)") (class "Default")
      (node (ref "LED2") (pin "1") (pinfunction "GRN_1") (pintype "bidirectional"))
      (node (ref "R2") (pin "2") (pinfunction "2_2") (pintype "passive"))
    )
    (net (code "86") (name "Net-(LED2-RED)") (class "Default")
      (node (ref "LED2") (pin "3") (pinfunction "RED_3") (pintype "bidirectional"))
      (node (ref "R7") (pin "2") (pinfunction "2_2") (pintype "passive"))
    )
    (net (code "87") (name "Net-(LED3-GRN)") (class "Default")
      (node (ref "LED3") (pin "1") (pinfunction "GRN_1") (pintype "bidirectional"))
      (node (ref "R10") (pin "2") (pinfunction "2_2") (pintype "passive"))
    )
    (net (code "88") (name "Net-(LED3-RED)") (class "Default")
      (node (ref "LED3") (pin "3") (pinfunction "RED_3") (pintype "bidirectional"))
      (node (ref "R13") (pin "2") (pinfunction "2_2") (pintype "passive"))
    )
    (net (code "89") (name "Net-(Q1B-2)") (class "Default")
      (node (ref "C4") (pin "2") (pinfunction "2_2") (pintype "passive"))
      (node (ref "Q1") (pin "3") (pinfunction "2_3") (pintype "passive"))
      (node (ref "R8") (pin "2") (pinfunction "2_2") (pintype "passive"))
    )
    (net (code "90") (name "RESET") (class "Default")
      (node (ref "C2") (pin "1") (pinfunction "1_1") (pintype "passive"))
      (node (ref "IC1") (pin "7") (pinfunction "NRST_7") (pintype "bidirectional"))
      (node (ref "JP6") (pin "4") (pinfunction "4_4") (pintype "passive"))
      (node (ref "R3") (pin "2") (pinfunction "2_2") (pintype "passive"))
    )
    (net (code "91") (name "RX") (class "Default")
      (node (ref "IC1") (pin "46") (pinfunction "PB9/SPI2_NSS/I2S2_WS/I2C1_SDA/USART3_RX/CAN_TX/TIM4_CH4_46") (pintype "bidirectional"))
      (node (ref "R4") (pin "2") (pinfunction "2_2") (pintype "passive"))
    )
    (net (code "92") (name "SHAPE_ATT") (class "Default")
      (node (ref "C54") (pin "1") (pinfunction "1_1") (pintype "passive"))
      (node (ref "IC2") (pin "4") (pinfunction "X7_4") (pintype "bidirectional"))
      (node (ref "R59") (pin "P$2") (pinfunction "S_P$2") (pintype "passive"))
    )
    (net (code "93") (name "SHAPE_POT") (class "Default")
      (node (ref "C23") (pin "1") (pinfunction "1_1") (pintype "passive"))
      (node (ref "IC1") (pin "10") (pinfunction "PA0/USART2_CTS/TIM2_CH1/TIM5_CH1/ADC_IN0_10") (pintype "bidirectional"))
      (node (ref "R12") (pin "P$2") (pinfunction "S_P$2") (pintype "passive"))
    )
    (net (code "94") (name "SHIFT_ATT") (class "Default")
      (node (ref "C55") (pin "1") (pinfunction "1_1") (pintype "passive"))
      (node (ref "IC2") (pin "15") (pinfunction "X2_15") (pintype "bidirectional"))
      (node (ref "R60") (pin "P$2") (pinfunction "S_P$2") (pintype "passive"))
    )
    (net (code "95") (name "SHIFT_POT") (class "Default")
      (node (ref "C45") (pin "1") (pinfunction "1_1") (pintype "passive"))
      (node (ref "IC2") (pin "14") (pinfunction "X1_14") (pintype "bidirectional"))
      (node (ref "R24") (pin "P$2") (pinfunction "S_P$2") (pintype "passive"))
    )
    (net (code "96") (name "SLOPE_ATT") (class "Default")
      (node (ref "C51") (pin "1") (pinfunction "1_1") (pintype "passive"))
      (node (ref "IC2") (pin "1") (pinfunction "X4_1") (pintype "bidirectional"))
      (node (ref "R56") (pin "P$2") (pinfunction "S_P$2") (pintype "passive"))
    )
    (net (code "97") (name "SLOPE_POT") (class "Default")
      (node (ref "C44") (pin "1") (pinfunction "1_1") (pintype "passive"))
      (node (ref "IC2") (pin "12") (pinfunction "X3_12") (pintype "bidirectional"))
      (node (ref "R23") (pin "P$2") (pinfunction "S_P$2") (pintype "passive"))
    )
    (net (code "98") (name "SMOOTHNESS_ATT") (class "Default")
      (node (ref "C53") (pin "1") (pinfunction "1_1") (pintype "passive"))
      (node (ref "IC2") (pin "5") (pinfunction "X5_5") (pintype "bidirectional"))
      (node (ref "R58") (pin "P$2") (pinfunction "S_P$2") (pintype "passive"))
    )
    (net (code "99") (name "SMOOTHNESS_POT") (class "Default")
      (node (ref "C35") (pin "1") (pinfunction "1_1") (pintype "passive"))
      (node (ref "IC2") (pin "13") (pinfunction "X0_13") (pintype "bidirectional"))
      (node (ref "R22") (pin "P$2") (pinfunction "S_P$2") (pintype "passive"))
    )
    (net (code "100") (name "SWCLK") (class "Default")
      (node (ref "IC1") (pin "37") (pinfunction "PA14/I2C1_SDA/JTCK-SWCLK_37") (pintype "bidirectional"))
      (node (ref "JP6") (pin "3") (pinfunction "3_3") (pintype "passive"))
    )
    (net (code "101") (name "SWDIO") (class "Default")
      (node (ref "IC1") (pin "34") (pinfunction "PA13/SPI1_MISO/I2S1_MCK/USART3_CTS/TIM4_CH3/TIM5_CH4/JTMS-SWDIO_34") (pintype "bidirectional"))
      (node (ref "JP6") (pin "2") (pinfunction "2_2") (pintype "passive"))
    )
    (net (code "102") (name "SW_MODE") (class "Default")
      (node (ref "IC1") (pin "33") (pinfunction "PA12/SPI1_SCK/I2S1_CK/USART1_RTS/CAN_TX/TIM4_CH2/TIM5_CH3_33") (pintype "bidirectional"))
      (node (ref "SW3") (pin "3") (pinfunction "3_3") (pintype "passive"))
      (node (ref "SW3") (pin "4") (pinfunction "4_4") (pintype "passive"))
    )
    (net (code "103") (name "SW_RANGE") (class "Default")
      (node (ref "IC1") (pin "12") (pinfunction "PA2/SPI3_MISO/I2S3_MCK/USART2_TX/TIM2_CH3/TIM5_CH3/ADC_IN2_12") (pintype "bidirectional"))
      (node (ref "SW2") (pin "3") (pinfunction "3_3") (pintype "passive"))
      (node (ref "SW2") (pin "4") (pinfunction "4_4") (pintype "passive"))
    )
    (net (code "104") (name "SW_SHIFT") (class "Default")
      (node (ref "IC1") (pin "2") (pinfunction "PC13/TIMESTAMP/RTC_TAMPER1_2") (pintype "bidirectional"))
      (node (ref "SW1") (pin "3") (pinfunction "3_3") (pintype "passive"))
      (node (ref "SW1") (pin "4") (pinfunction "4_4") (pintype "passive"))
    )
    (net (code "105") (name "TX") (class "Default")
      (node (ref "IC1") (pin "45") (pinfunction "PB8/SPI2_SCK/I2S2_CK/I2C1_SCL/USART3_TX/CAN_RX/TIM4_CH3_45") (pintype "bidirectional"))
      (node (ref "R5") (pin "2") (pinfunction "2_2") (pintype "passive"))
    )
    (net (code "106") (name "VCC") (class "Default")
      (node (ref "C24") (pin "+") (pinfunction "+_+") (pintype "passive"))
      (node (ref "C48") (pin "1") (pinfunction "1_1") (pintype "passive"))
      (node (ref "C49") (pin "1") (pinfunction "1_1") (pintype "passive"))
      (node (ref "IC8") (pin "4") (pinfunction "V+_4") (pintype "power_in"))
      (node (ref "IC9") (pin "4") (pinfunction "V+_4") (pintype "power_in"))
      (node (ref "L2") (pin "1") (pinfunction "1_1") (pintype "passive"))
    )
    (net (code "107") (name "VEE") (class "Default")
      (node (ref "C26") (pin "-") (pinfunction "-_-") (pintype "passive"))
      (node (ref "C33") (pin "2") (pinfunction "2_2") (pintype "passive"))
      (node (ref "C34") (pin "2") (pinfunction "2_2") (pintype "passive"))
      (node (ref "IC8") (pin "11") (pinfunction "V-_11") (pintype "power_in"))
      (node (ref "IC9") (pin "11") (pinfunction "V-_11") (pintype "power_in"))
      (node (ref "L4") (pin "1") (pinfunction "1_1") (pintype "passive"))
      (node (ref "R46") (pin "1") (pinfunction "1_1") (pintype "passive"))
    )
    (net (code "108") (name "VREF") (class "Default")
      (node (ref "C18") (pin "1") (pinfunction "1_1") (pintype "passive"))
      (node (ref "IC4") (pin "3") (pinfunction "VREFH_3") (pintype "bidirectional"))
      (node (ref "R14") (pin "2") (pinfunction "2_2") (pintype "passive"))
    )
    (net (code "109") (name "VREF_BIAS") (class "Default")
      (node (ref "C21") (pin "1") (pinfunction "1_1") (pintype "passive"))
      (node (ref "IC8") (pin "10") (pinfunction "+IN_10") (pintype "input"))
      (node (ref "IC8") (pin "12") (pinfunction "+IN_12") (pintype "input"))
      (node (ref "IC9") (pin "10") (pinfunction "+IN_10") (pintype "input"))
      (node (ref "IC9") (pin "12") (pinfunction "+IN_12") (pintype "input"))
      (node (ref "R14") (pin "1") (pinfunction "1_1") (pintype "passive"))
      (node (ref "R15") (pin "2") (pinfunction "2_2") (pintype "passive"))
    )
    (net (code "110") (name "unconnected-(IC1-PA15{slash}SPI1_NSS{slash}I2S1_WS{slash}SPI3_NSS{slash}I2S3_WS{slash}I2C1_SCL{slash}TIM2_CH1_ETR{slash}JTDI-Pad38)") (class "Default")
      (node (ref "IC1") (pin "38") (pinfunction "PA15/SPI1_NSS/I2S1_WS/SPI3_NSS/I2S3_WS/I2C1_SCL/TIM2_CH1_ETR/JTDI_38") (pintype "bidirectional"))
    )
    (net (code "111") (name "unconnected-(IC1-PB7{slash}I2C1_SDA{slash}USART1_RX{slash}TIM4_CH2-Pad43)") (class "Default")
      (node (ref "IC1") (pin "43") (pinfunction "PB7/I2C1_SDA/USART1_RX/TIM4_CH2_43") (pintype "bidirectional"))
    )
    (net (code "112") (name "unconnected-(IC1-PC14{slash}OSC32_IN-Pad3)") (class "Default")
      (node (ref "IC1") (pin "3") (pinfunction "PC14/OSC32_IN_3") (pintype "bidirectional"))
    )
    (net (code "113") (name "unconnected-(IC1-PC15{slash}OSC32_OUT-Pad4)") (class "Default")
      (node (ref "IC1") (pin "4") (pinfunction "PC15/OSC32_OUT_4") (pintype "bidirectional"))
    )
    (net (code "114") (name "unconnected-(J9-2-PadP2)") (class "Default")
      (node (ref "J9") (pin "P2") (pinfunction "2_P2") (pintype "passive"))
    )
    (net (code "115") (name "unconnected-(J10-2-PadP2)") (class "Default")
      (node (ref "J10") (pin "P2") (pinfunction "2_P2") (pintype "passive"))
    )
    (net (code "116") (name "unconnected-(J11-2-PadP2)") (class "Default")
      (node (ref "J11") (pin "P2") (pinfunction "2_P2") (pintype "passive"))
    )
    (net (code "117") (name "unconnected-(J12-2-PadP2)") (class "Default")
      (node (ref "J12") (pin "P2") (pinfunction "2_P2") (pintype "passive"))
    )
  )
)
